# unitbase_anayuki.net
KiCad netlist of a schematic drawn in EAGLE
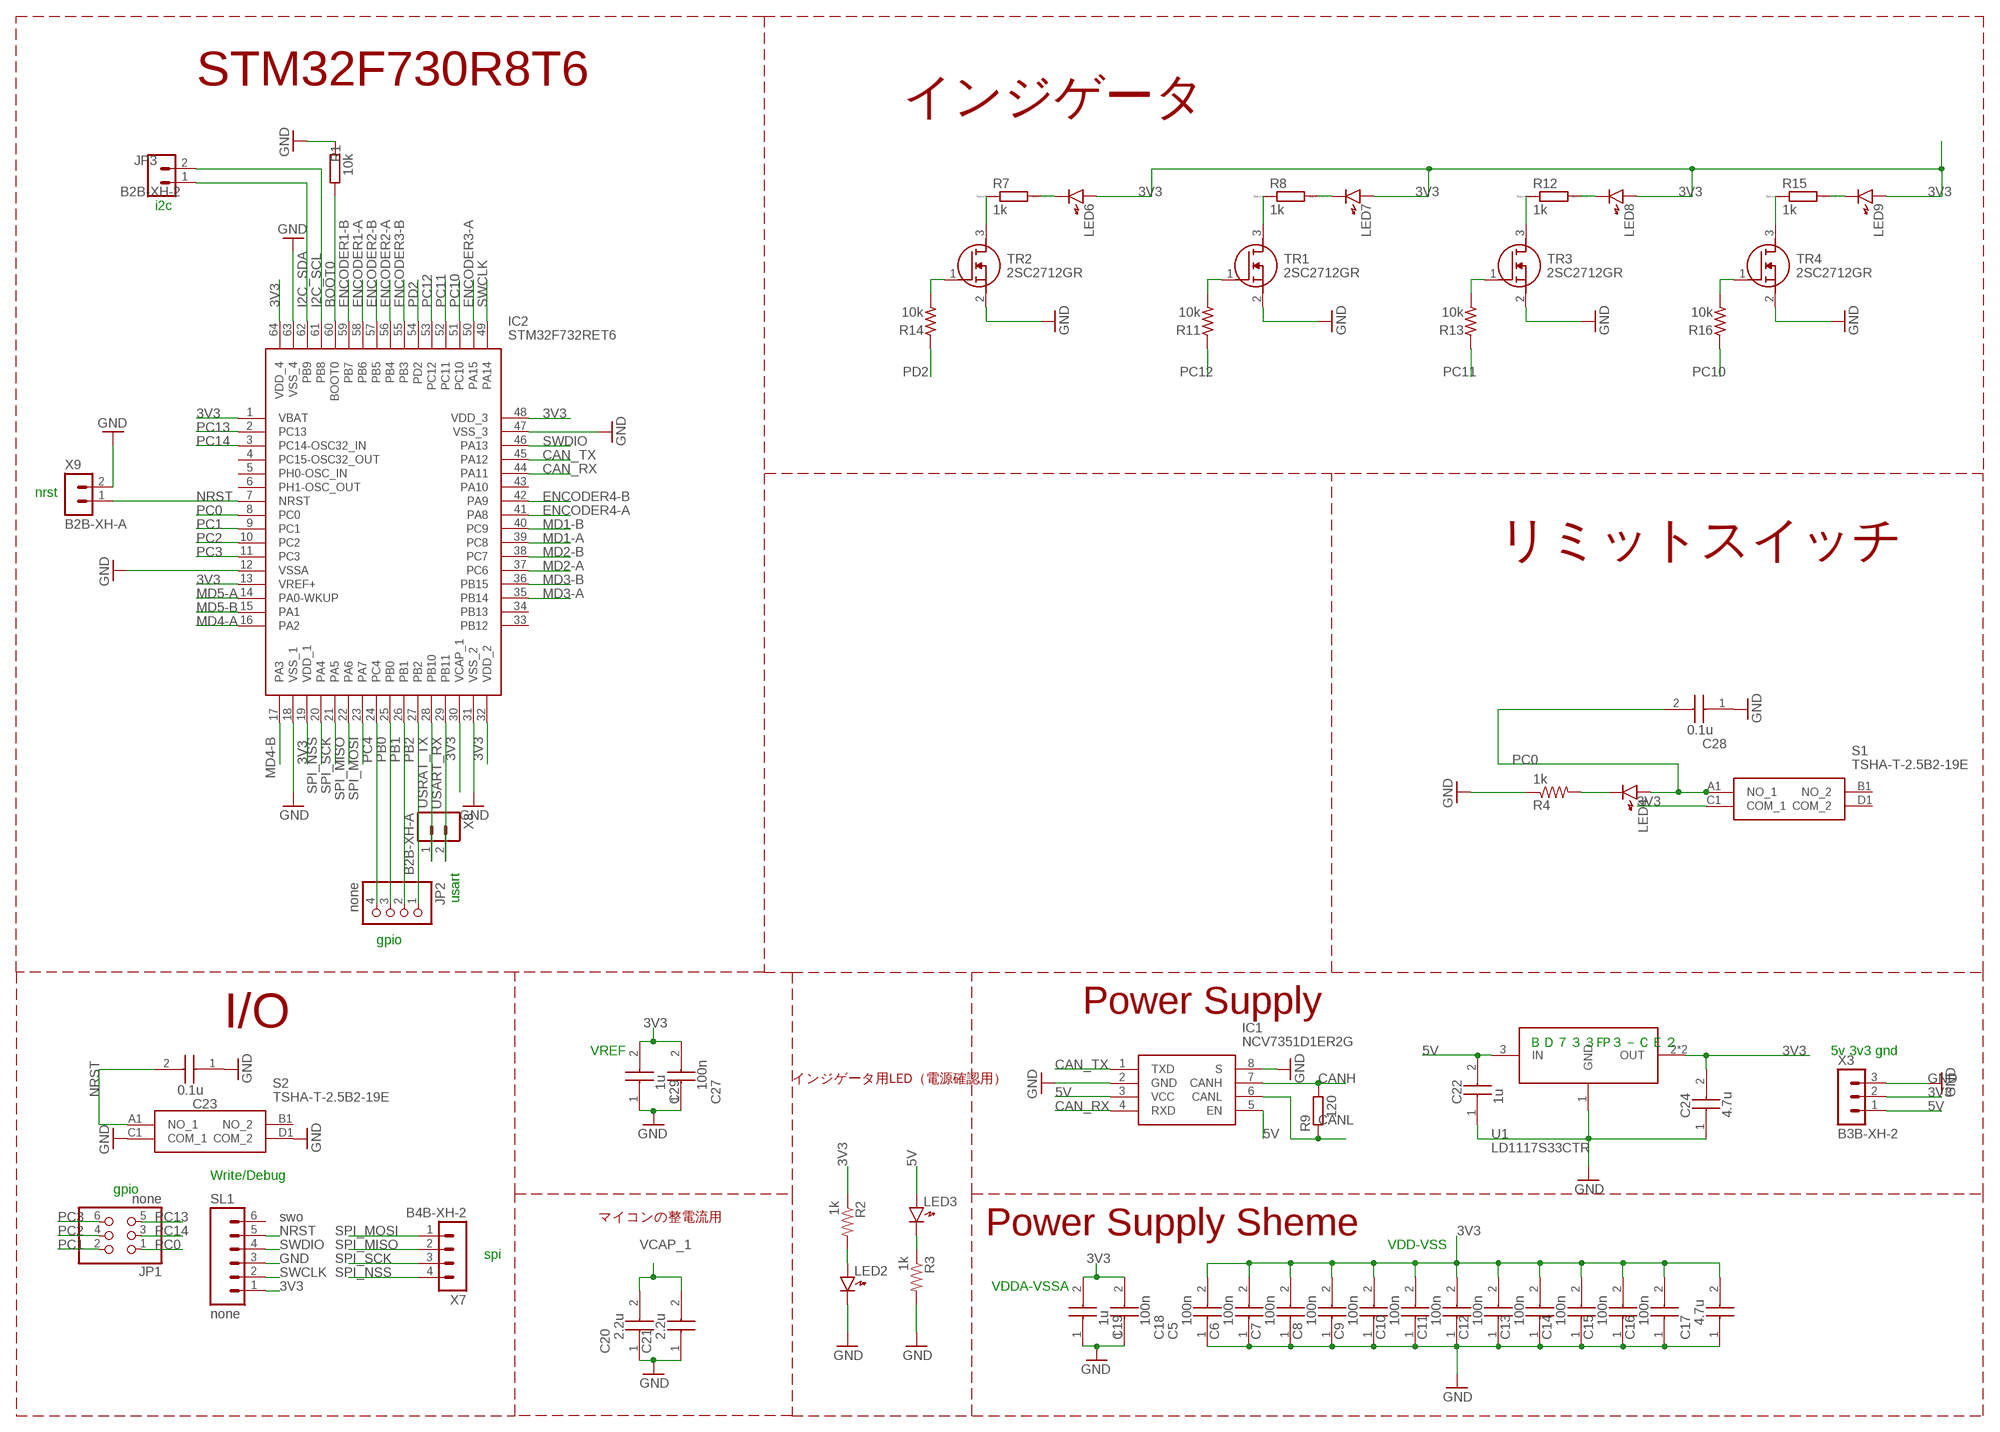
[diagram p0: schematic, sheet 1]
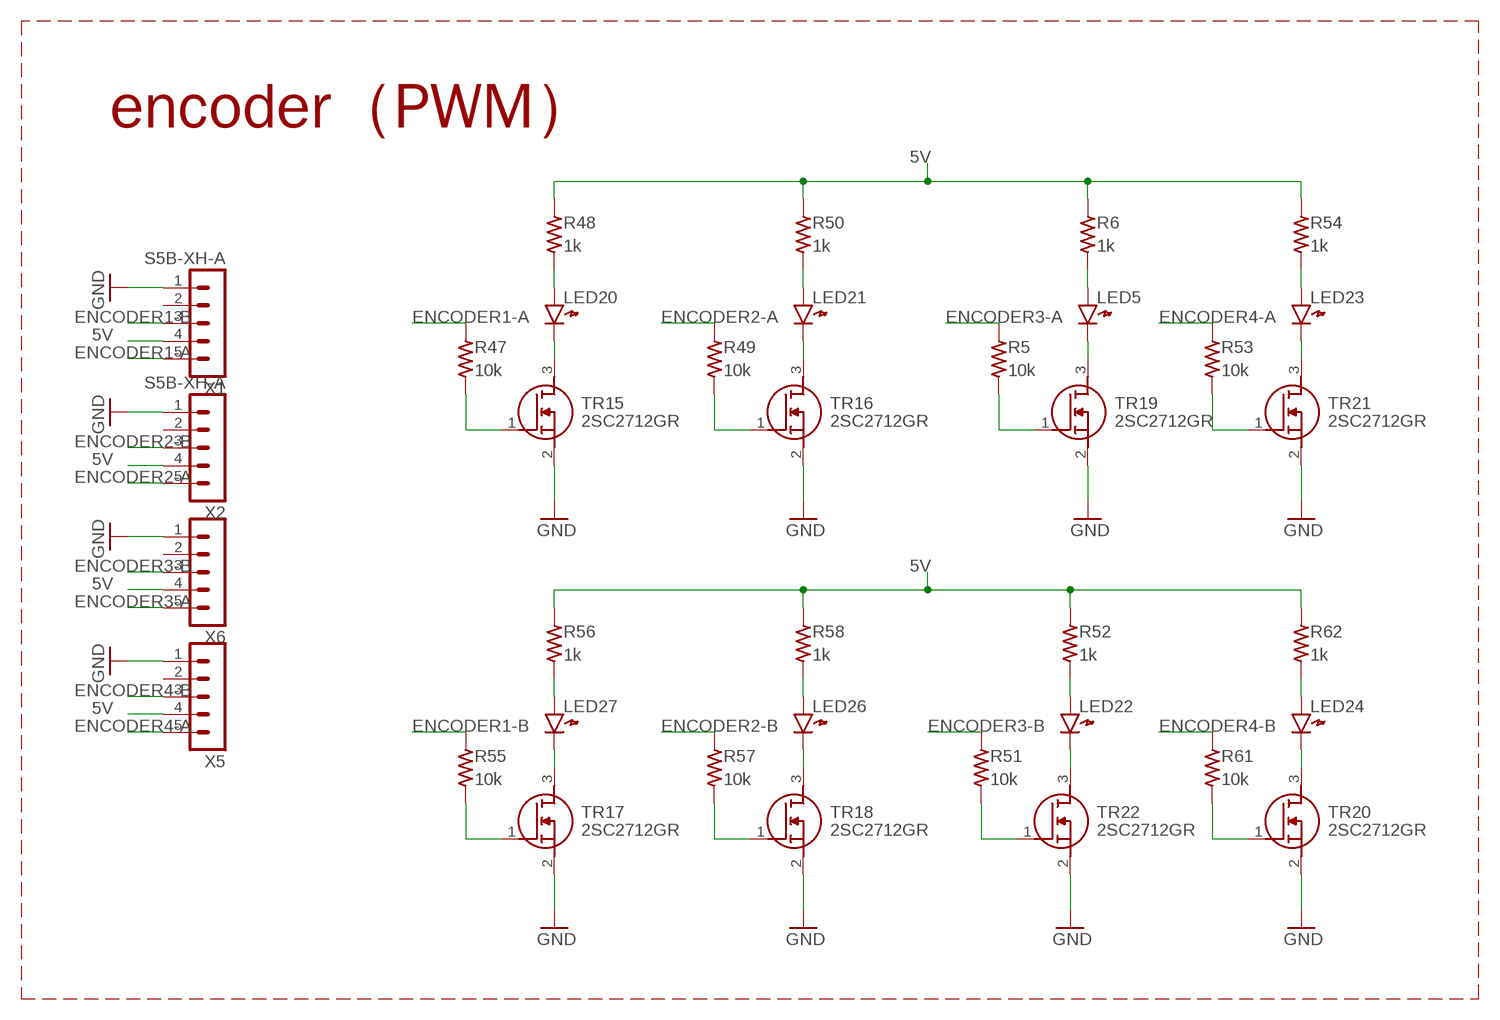
[diagram p1: schematic, sheet 2]
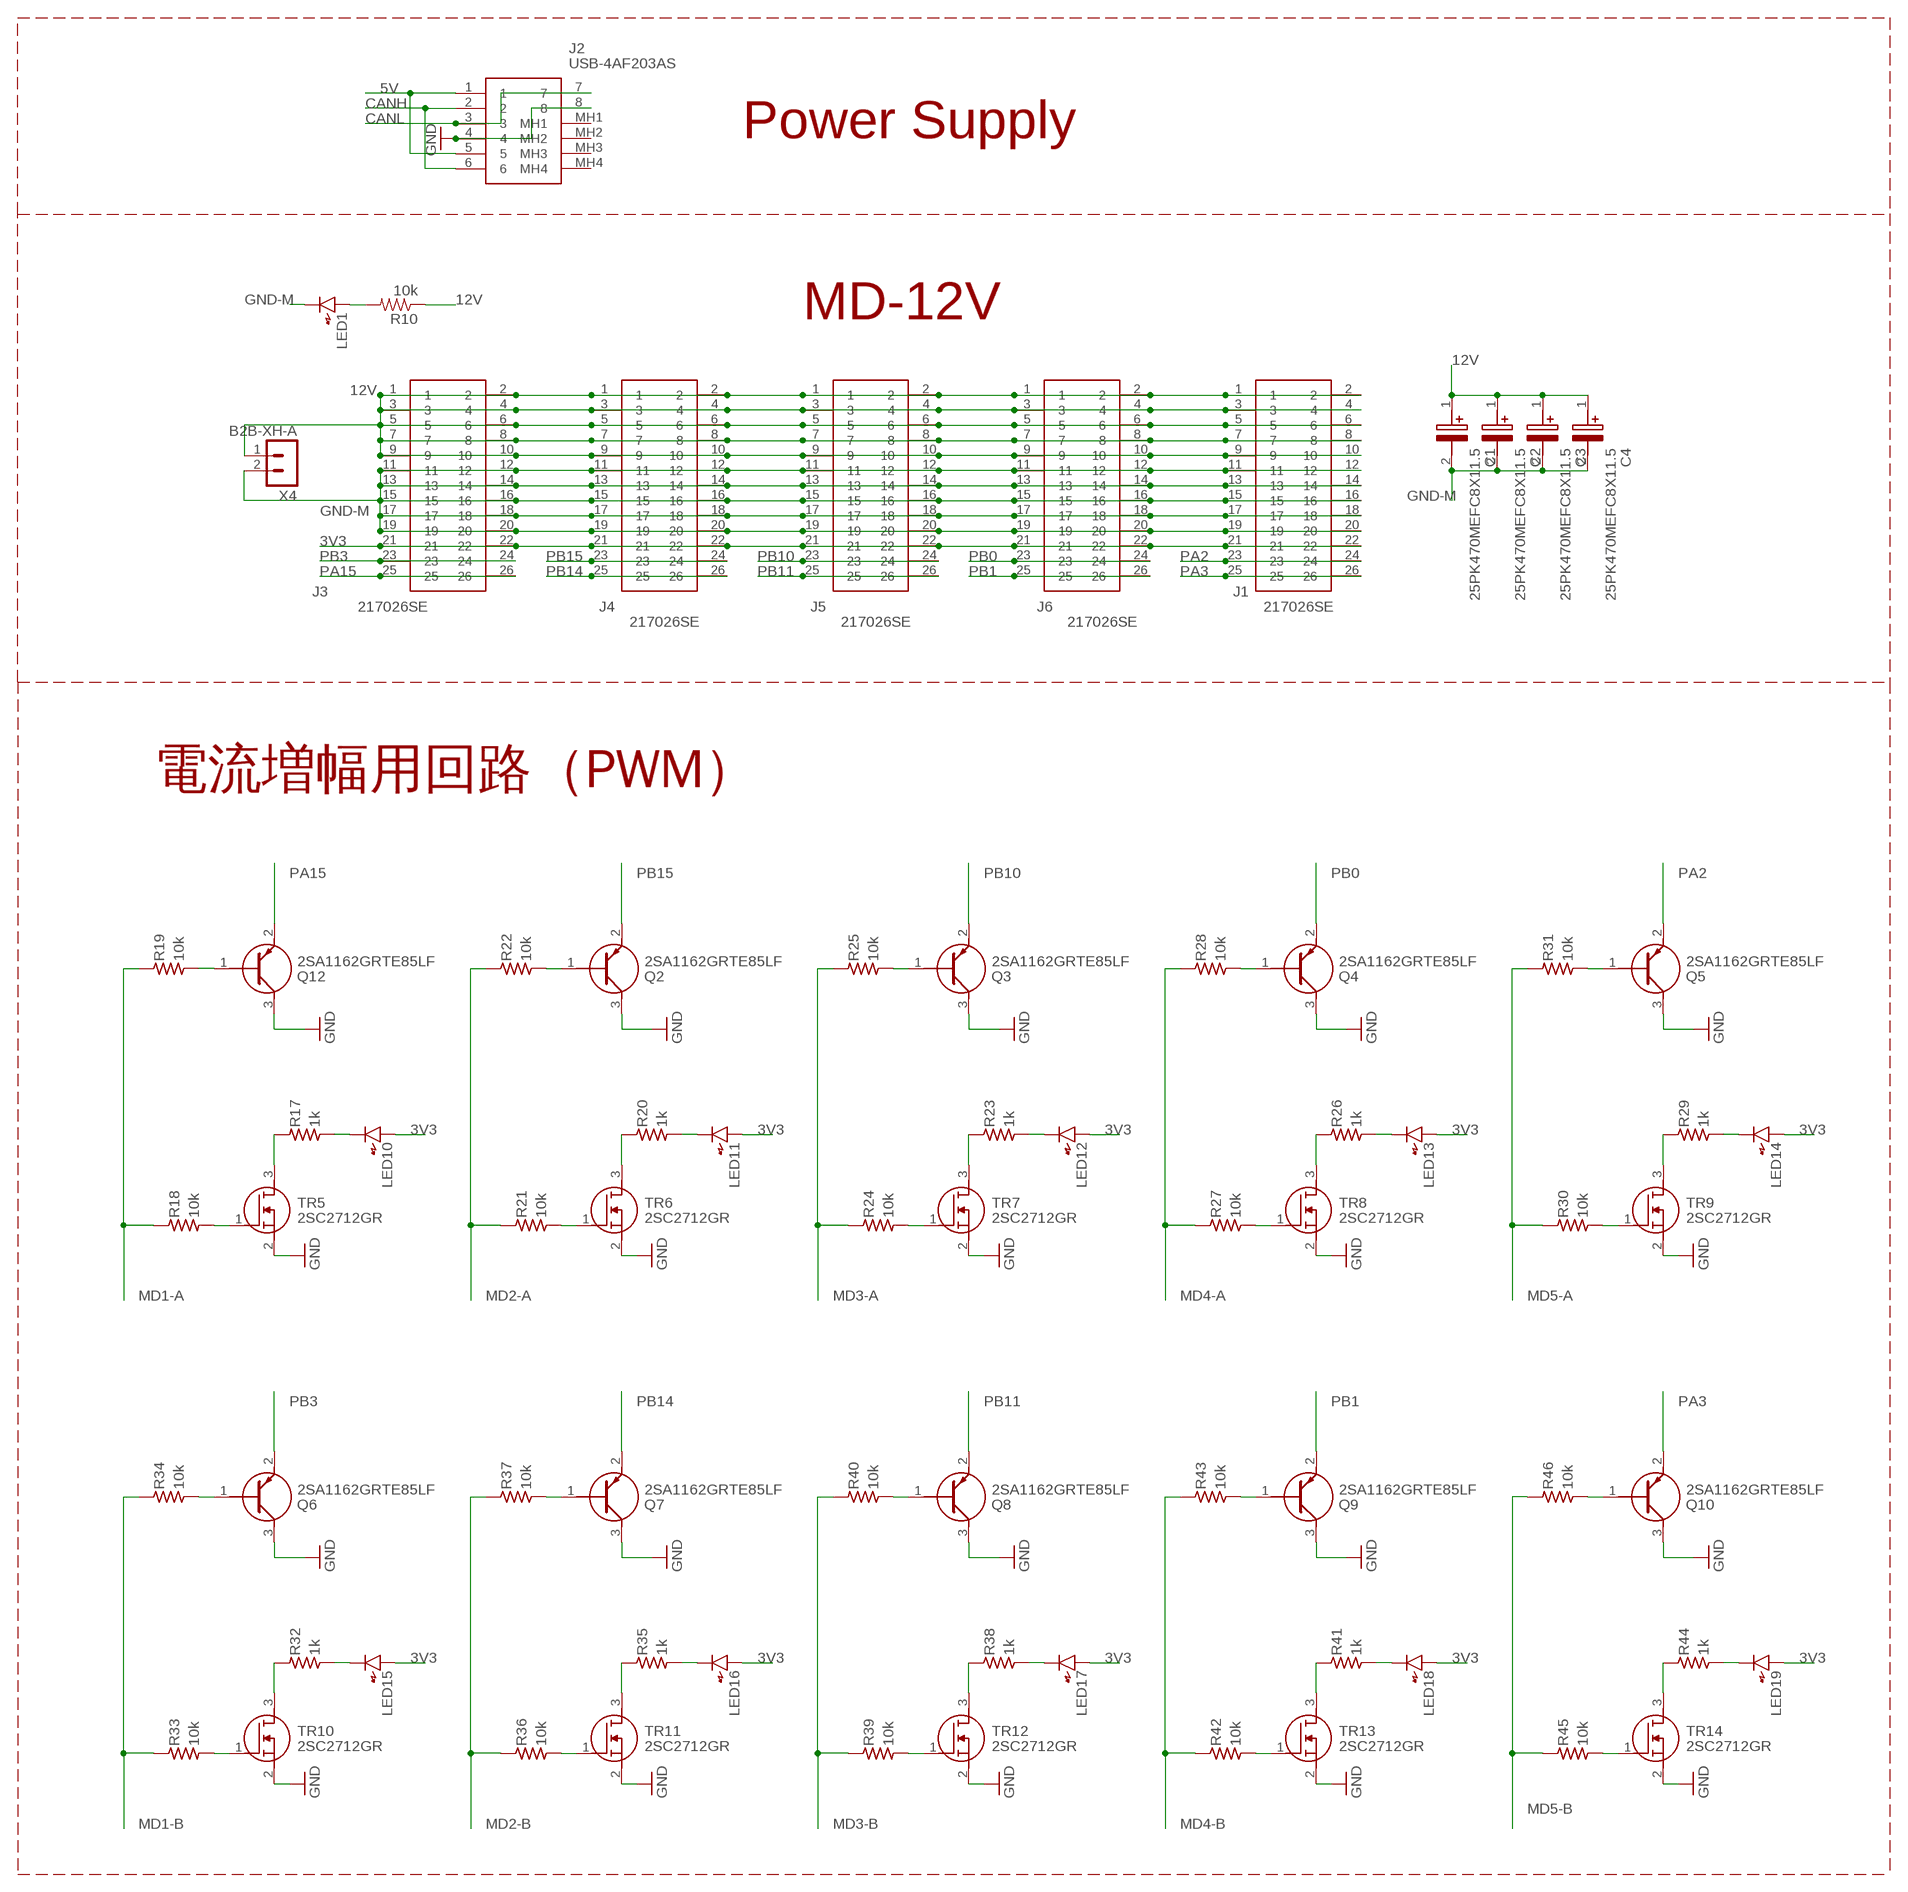
[diagram p2: schematic, sheet 3]

(export (version "E")
  (design (tool "Eeschema 10.0.6"))
  (components
    (comp (ref "C1")
      (value "25PK470MEFC8X11.5")
      (footprint "eagle-import:CAPPRD350W60D825H1150")
      (fields (field (name "MOUSER_PART_NUMBER") "232-25PK470MEFC8X115"))
      (libsource (lib "eagle-import") (part "25PK470MEFC8X11.5"))
    )
    (comp (ref "C2")
      (value "25PK470MEFC8X11.5")
      (footprint "eagle-import:CAPPRD350W60D825H1150")
      (fields (field (name "MOUSER_PART_NUMBER") "232-25PK470MEFC8X115"))
      (libsource (lib "eagle-import") (part "25PK470MEFC8X11.5"))
    )
    (comp (ref "C3")
      (value "25PK470MEFC8X11.5")
      (footprint "eagle-import:CAPPRD350W60D825H1150")
      (fields (field (name "MOUSER_PART_NUMBER") "232-25PK470MEFC8X115"))
      (libsource (lib "eagle-import") (part "25PK470MEFC8X11.5"))
    )
    (comp (ref "C4")
      (value "25PK470MEFC8X11.5")
      (footprint "eagle-import:CAPPRD350W60D825H1150")
      (fields (field (name "MOUSER_PART_NUMBER") "232-25PK470MEFC8X115"))
      (libsource (lib "eagle-import") (part "25PK470MEFC8X11.5"))
    )
    (comp (ref "J1")
      (value "217026SE")
      (footprint "eagle-import:217026SE")
      (libsource (lib "eagle-import") (part "217026SE"))
    )
    (comp (ref "J2")
      (value "USB-4AF203AS")
      (footprint "eagle-import:USB4AF203AS")
      (libsource (lib "eagle-import") (part "USB-4AF203AS"))
    )
    (comp (ref "J3")
      (value "217026SE")
      (footprint "eagle-import:217026SE")
      (libsource (lib "eagle-import") (part "217026SE"))
    )
    (comp (ref "J4")
      (value "217026SE")
      (footprint "eagle-import:217026SE")
      (libsource (lib "eagle-import") (part "217026SE"))
    )
    (comp (ref "J5")
      (value "217026SE")
      (footprint "eagle-import:217026SE")
      (libsource (lib "eagle-import") (part "217026SE"))
    )
    (comp (ref "J6")
      (value "217026SE")
      (footprint "eagle-import:217026SE")
      (libsource (lib "eagle-import") (part "217026SE"))
    )
    (comp (ref "LED1")
      (value "LED1608")
      (footprint "eagle-import:LED1608")
      (libsource (lib "eagle-import") (part "LED1608"))
    )
    (comp (ref "LED10")
      (value "LED1608")
      (footprint "eagle-import:LED1608")
      (libsource (lib "eagle-import") (part "LED1608"))
    )
    (comp (ref "LED11")
      (value "LED1608")
      (footprint "eagle-import:LED1608")
      (libsource (lib "eagle-import") (part "LED1608"))
    )
    (comp (ref "LED12")
      (value "LED1608")
      (footprint "eagle-import:LED1608")
      (libsource (lib "eagle-import") (part "LED1608"))
    )
    (comp (ref "LED13")
      (value "LED1608")
      (footprint "eagle-import:LED1608")
      (libsource (lib "eagle-import") (part "LED1608"))
    )
    (comp (ref "LED14")
      (value "LED1608")
      (footprint "eagle-import:LED1608")
      (libsource (lib "eagle-import") (part "LED1608"))
    )
    (comp (ref "LED15")
      (value "LED1608")
      (footprint "eagle-import:LED1608")
      (libsource (lib "eagle-import") (part "LED1608"))
    )
    (comp (ref "LED16")
      (value "LED1608")
      (footprint "eagle-import:LED1608")
      (libsource (lib "eagle-import") (part "LED1608"))
    )
    (comp (ref "LED17")
      (value "LED1608")
      (footprint "eagle-import:LED1608")
      (libsource (lib "eagle-import") (part "LED1608"))
    )
    (comp (ref "LED18")
      (value "LED1608")
      (footprint "eagle-import:LED1608")
      (libsource (lib "eagle-import") (part "LED1608"))
    )
    (comp (ref "LED19")
      (value "LED1608")
      (footprint "eagle-import:LED1608")
      (libsource (lib "eagle-import") (part "LED1608"))
    )
    (comp (ref "Q2")
      (value "2SA1162GRTE85LF")
      (footprint "eagle-import:2SA1162GRTE85LF")
      (libsource (lib "eagle-import") (part "2SA1162GRTE85LF"))
    )
    (comp (ref "Q3")
      (value "2SA1162GRTE85LF")
      (footprint "eagle-import:2SA1162GRTE85LF")
      (libsource (lib "eagle-import") (part "2SA1162GRTE85LF"))
    )
    (comp (ref "Q4")
      (value "2SA1162GRTE85LF")
      (footprint "eagle-import:2SA1162GRTE85LF")
      (libsource (lib "eagle-import") (part "2SA1162GRTE85LF"))
    )
    (comp (ref "Q5")
      (value "2SA1162GRTE85LF")
      (footprint "eagle-import:2SA1162GRTE85LF")
      (libsource (lib "eagle-import") (part "2SA1162GRTE85LF"))
    )
    (comp (ref "Q6")
      (value "2SA1162GRTE85LF")
      (footprint "eagle-import:2SA1162GRTE85LF")
      (libsource (lib "eagle-import") (part "2SA1162GRTE85LF"))
    )
    (comp (ref "Q7")
      (value "2SA1162GRTE85LF")
      (footprint "eagle-import:2SA1162GRTE85LF")
      (libsource (lib "eagle-import") (part "2SA1162GRTE85LF"))
    )
    (comp (ref "Q8")
      (value "2SA1162GRTE85LF")
      (footprint "eagle-import:2SA1162GRTE85LF")
      (libsource (lib "eagle-import") (part "2SA1162GRTE85LF"))
    )
    (comp (ref "Q9")
      (value "2SA1162GRTE85LF")
      (footprint "eagle-import:2SA1162GRTE85LF")
      (libsource (lib "eagle-import") (part "2SA1162GRTE85LF"))
    )
    (comp (ref "Q10")
      (value "2SA1162GRTE85LF")
      (footprint "eagle-import:2SA1162GRTE85LF")
      (libsource (lib "eagle-import") (part "2SA1162GRTE85LF"))
    )
    (comp (ref "Q12")
      (value "2SA1162GRTE85LF")
      (footprint "eagle-import:2SA1162GRTE85LF")
      (libsource (lib "eagle-import") (part "2SA1162GRTE85LF"))
    )
    (comp (ref "R10")
      (value "10k")
      (footprint "eagle-import:R0603")
      (libsource (lib "eagle-import") (part "R-US_R0603"))
    )
    (comp (ref "R17")
      (value "1k")
      (footprint "eagle-import:SMD1608")
      (libsource (lib "eagle-import") (part "RESISTOR-US1608"))
    )
    (comp (ref "R18")
      (value "10k")
      (footprint "eagle-import:SMD1608")
      (libsource (lib "eagle-import") (part "RESISTOR-US1608"))
    )
    (comp (ref "R19")
      (value "10k")
      (footprint "eagle-import:SMD1608")
      (libsource (lib "eagle-import") (part "RESISTOR-US1608"))
    )
    (comp (ref "R20")
      (value "1k")
      (footprint "eagle-import:SMD1608")
      (libsource (lib "eagle-import") (part "RESISTOR-US1608"))
    )
    (comp (ref "R21")
      (value "10k")
      (footprint "eagle-import:SMD1608")
      (libsource (lib "eagle-import") (part "RESISTOR-US1608"))
    )
    (comp (ref "R22")
      (value "10k")
      (footprint "eagle-import:SMD1608")
      (libsource (lib "eagle-import") (part "RESISTOR-US1608"))
    )
    (comp (ref "R23")
      (value "1k")
      (footprint "eagle-import:SMD1608")
      (libsource (lib "eagle-import") (part "RESISTOR-US1608"))
    )
    (comp (ref "R24")
      (value "10k")
      (footprint "eagle-import:SMD1608")
      (libsource (lib "eagle-import") (part "RESISTOR-US1608"))
    )
    (comp (ref "R25")
      (value "10k")
      (footprint "eagle-import:SMD1608")
      (libsource (lib "eagle-import") (part "RESISTOR-US1608"))
    )
    (comp (ref "R26")
      (value "1k")
      (footprint "eagle-import:SMD1608")
      (libsource (lib "eagle-import") (part "RESISTOR-US1608"))
    )
    (comp (ref "R27")
      (value "10k")
      (footprint "eagle-import:SMD1608")
      (libsource (lib "eagle-import") (part "RESISTOR-US1608"))
    )
    (comp (ref "R28")
      (value "10k")
      (footprint "eagle-import:SMD1608")
      (libsource (lib "eagle-import") (part "RESISTOR-US1608"))
    )
    (comp (ref "R29")
      (value "1k")
      (footprint "eagle-import:SMD1608")
      (libsource (lib "eagle-import") (part "RESISTOR-US1608"))
    )
    (comp (ref "R30")
      (value "10k")
      (footprint "eagle-import:SMD1608")
      (libsource (lib "eagle-import") (part "RESISTOR-US1608"))
    )
    (comp (ref "R31")
      (value "10k")
      (footprint "eagle-import:SMD1608")
      (libsource (lib "eagle-import") (part "RESISTOR-US1608"))
    )
    (comp (ref "R32")
      (value "1k")
      (footprint "eagle-import:SMD1608")
      (libsource (lib "eagle-import") (part "RESISTOR-US1608"))
    )
    (comp (ref "R33")
      (value "10k")
      (footprint "eagle-import:SMD1608")
      (libsource (lib "eagle-import") (part "RESISTOR-US1608"))
    )
    (comp (ref "R34")
      (value "10k")
      (footprint "eagle-import:SMD1608")
      (libsource (lib "eagle-import") (part "RESISTOR-US1608"))
    )
    (comp (ref "R35")
      (value "1k")
      (footprint "eagle-import:SMD1608")
      (libsource (lib "eagle-import") (part "RESISTOR-US1608"))
    )
    (comp (ref "R36")
      (value "10k")
      (footprint "eagle-import:SMD1608")
      (libsource (lib "eagle-import") (part "RESISTOR-US1608"))
    )
    (comp (ref "R37")
      (value "10k")
      (footprint "eagle-import:SMD1608")
      (libsource (lib "eagle-import") (part "RESISTOR-US1608"))
    )
    (comp (ref "R38")
      (value "1k")
      (footprint "eagle-import:SMD1608")
      (libsource (lib "eagle-import") (part "RESISTOR-US1608"))
    )
    (comp (ref "R39")
      (value "10k")
      (footprint "eagle-import:SMD1608")
      (libsource (lib "eagle-import") (part "RESISTOR-US1608"))
    )
    (comp (ref "R40")
      (value "10k")
      (footprint "eagle-import:SMD1608")
      (libsource (lib "eagle-import") (part "RESISTOR-US1608"))
    )
    (comp (ref "R41")
      (value "1k")
      (footprint "eagle-import:SMD1608")
      (libsource (lib "eagle-import") (part "RESISTOR-US1608"))
    )
    (comp (ref "R42")
      (value "10k")
      (footprint "eagle-import:SMD1608")
      (libsource (lib "eagle-import") (part "RESISTOR-US1608"))
    )
    (comp (ref "R43")
      (value "10k")
      (footprint "eagle-import:SMD1608")
      (libsource (lib "eagle-import") (part "RESISTOR-US1608"))
    )
    (comp (ref "R44")
      (value "1k")
      (footprint "eagle-import:SMD1608")
      (libsource (lib "eagle-import") (part "RESISTOR-US1608"))
    )
    (comp (ref "R45")
      (value "10k")
      (footprint "eagle-import:SMD1608")
      (libsource (lib "eagle-import") (part "RESISTOR-US1608"))
    )
    (comp (ref "R46")
      (value "10k")
      (footprint "eagle-import:SMD1608")
      (libsource (lib "eagle-import") (part "RESISTOR-US1608"))
    )
    (comp (ref "TR5")
      (value "2SC2712GR")
      (footprint "eagle-import:SOT-23")
      (libsource (lib "eagle-import") (part "SOT-23_NMOS"))
    )
    (comp (ref "TR6")
      (value "2SC2712GR")
      (footprint "eagle-import:SOT-23")
      (libsource (lib "eagle-import") (part "SOT-23_NMOS"))
    )
    (comp (ref "TR7")
      (value "2SC2712GR")
      (footprint "eagle-import:SOT-23")
      (libsource (lib "eagle-import") (part "SOT-23_NMOS"))
    )
    (comp (ref "TR8")
      (value "2SC2712GR")
      (footprint "eagle-import:SOT-23")
      (libsource (lib "eagle-import") (part "SOT-23_NMOS"))
    )
    (comp (ref "TR9")
      (value "2SC2712GR")
      (footprint "eagle-import:SOT-23")
      (libsource (lib "eagle-import") (part "SOT-23_NMOS"))
    )
    (comp (ref "TR10")
      (value "2SC2712GR")
      (footprint "eagle-import:SOT-23")
      (libsource (lib "eagle-import") (part "SOT-23_NMOS"))
    )
    (comp (ref "TR11")
      (value "2SC2712GR")
      (footprint "eagle-import:SOT-23")
      (libsource (lib "eagle-import") (part "SOT-23_NMOS"))
    )
    (comp (ref "TR12")
      (value "2SC2712GR")
      (footprint "eagle-import:SOT-23")
      (libsource (lib "eagle-import") (part "SOT-23_NMOS"))
    )
    (comp (ref "TR13")
      (value "2SC2712GR")
      (footprint "eagle-import:SOT-23")
      (libsource (lib "eagle-import") (part "SOT-23_NMOS"))
    )
    (comp (ref "TR14")
      (value "2SC2712GR")
      (footprint "eagle-import:SOT-23")
      (libsource (lib "eagle-import") (part "SOT-23_NMOS"))
    )
    (comp (ref "X4")
      (value "B2B-XH-A")
      (footprint "eagle-import:B2B-XH-A")
      (libsource (lib "eagle-import") (part "B2B-XH-A"))
    )
    (comp (ref "LED5")
      (value "LED1608")
      (footprint "eagle-import:LED1608")
      (libsource (lib "eagle-import") (part "LED1608"))
    )
    (comp (ref "LED20")
      (value "LED1608")
      (footprint "eagle-import:LED1608")
      (libsource (lib "eagle-import") (part "LED1608"))
    )
    (comp (ref "LED21")
      (value "LED1608")
      (footprint "eagle-import:LED1608")
      (libsource (lib "eagle-import") (part "LED1608"))
    )
    (comp (ref "LED22")
      (value "LED1608")
      (footprint "eagle-import:LED1608")
      (libsource (lib "eagle-import") (part "LED1608"))
    )
    (comp (ref "LED23")
      (value "LED1608")
      (footprint "eagle-import:LED1608")
      (libsource (lib "eagle-import") (part "LED1608"))
    )
    (comp (ref "LED24")
      (value "LED1608")
      (footprint "eagle-import:LED1608")
      (libsource (lib "eagle-import") (part "LED1608"))
    )
    (comp (ref "LED26")
      (value "LED1608")
      (footprint "eagle-import:LED1608")
      (libsource (lib "eagle-import") (part "LED1608"))
    )
    (comp (ref "LED27")
      (value "LED1608")
      (footprint "eagle-import:LED1608")
      (libsource (lib "eagle-import") (part "LED1608"))
    )
    (comp (ref "R5")
      (value "10k")
      (footprint "eagle-import:SMD1608")
      (libsource (lib "eagle-import") (part "RESISTOR-US1608"))
    )
    (comp (ref "R6")
      (value "1k")
      (footprint "eagle-import:SMD1608")
      (libsource (lib "eagle-import") (part "RESISTOR-US1608"))
    )
    (comp (ref "R47")
      (value "10k")
      (footprint "eagle-import:SMD1608")
      (libsource (lib "eagle-import") (part "RESISTOR-US1608"))
    )
    (comp (ref "R48")
      (value "1k")
      (footprint "eagle-import:SMD1608")
      (libsource (lib "eagle-import") (part "RESISTOR-US1608"))
    )
    (comp (ref "R49")
      (value "10k")
      (footprint "eagle-import:SMD1608")
      (libsource (lib "eagle-import") (part "RESISTOR-US1608"))
    )
    (comp (ref "R50")
      (value "1k")
      (footprint "eagle-import:SMD1608")
      (libsource (lib "eagle-import") (part "RESISTOR-US1608"))
    )
    (comp (ref "R51")
      (value "10k")
      (footprint "eagle-import:SMD1608")
      (libsource (lib "eagle-import") (part "RESISTOR-US1608"))
    )
    (comp (ref "R52")
      (value "1k")
      (footprint "eagle-import:SMD1608")
      (libsource (lib "eagle-import") (part "RESISTOR-US1608"))
    )
    (comp (ref "R53")
      (value "10k")
      (footprint "eagle-import:SMD1608")
      (libsource (lib "eagle-import") (part "RESISTOR-US1608"))
    )
    (comp (ref "R54")
      (value "1k")
      (footprint "eagle-import:SMD1608")
      (libsource (lib "eagle-import") (part "RESISTOR-US1608"))
    )
    (comp (ref "R55")
      (value "10k")
      (footprint "eagle-import:SMD1608")
      (libsource (lib "eagle-import") (part "RESISTOR-US1608"))
    )
    (comp (ref "R56")
      (value "1k")
      (footprint "eagle-import:SMD1608")
      (libsource (lib "eagle-import") (part "RESISTOR-US1608"))
    )
    (comp (ref "R57")
      (value "10k")
      (footprint "eagle-import:SMD1608")
      (libsource (lib "eagle-import") (part "RESISTOR-US1608"))
    )
    (comp (ref "R58")
      (value "1k")
      (footprint "eagle-import:SMD1608")
      (libsource (lib "eagle-import") (part "RESISTOR-US1608"))
    )
    (comp (ref "R61")
      (value "10k")
      (footprint "eagle-import:SMD1608")
      (libsource (lib "eagle-import") (part "RESISTOR-US1608"))
    )
    (comp (ref "R62")
      (value "1k")
      (footprint "eagle-import:SMD1608")
      (libsource (lib "eagle-import") (part "RESISTOR-US1608"))
    )
    (comp (ref "TR15")
      (value "2SC2712GR")
      (footprint "eagle-import:SOT-23")
      (libsource (lib "eagle-import") (part "SOT-23_NMOS"))
    )
    (comp (ref "TR16")
      (value "2SC2712GR")
      (footprint "eagle-import:SOT-23")
      (libsource (lib "eagle-import") (part "SOT-23_NMOS"))
    )
    (comp (ref "TR17")
      (value "2SC2712GR")
      (footprint "eagle-import:SOT-23")
      (libsource (lib "eagle-import") (part "SOT-23_NMOS"))
    )
    (comp (ref "TR18")
      (value "2SC2712GR")
      (footprint "eagle-import:SOT-23")
      (libsource (lib "eagle-import") (part "SOT-23_NMOS"))
    )
    (comp (ref "TR19")
      (value "2SC2712GR")
      (footprint "eagle-import:SOT-23")
      (libsource (lib "eagle-import") (part "SOT-23_NMOS"))
    )
    (comp (ref "TR20")
      (value "2SC2712GR")
      (footprint "eagle-import:SOT-23")
      (libsource (lib "eagle-import") (part "SOT-23_NMOS"))
    )
    (comp (ref "TR21")
      (value "2SC2712GR")
      (footprint "eagle-import:SOT-23")
      (libsource (lib "eagle-import") (part "SOT-23_NMOS"))
    )
    (comp (ref "TR22")
      (value "2SC2712GR")
      (footprint "eagle-import:SOT-23")
      (libsource (lib "eagle-import") (part "SOT-23_NMOS"))
    )
    (comp (ref "X1")
      (value "S5B-XH-A")
      (footprint "eagle-import:S5B-XH-A")
      (libsource (lib "eagle-import") (part "S5B-XH-A"))
    )
    (comp (ref "X2")
      (value "S5B-XH-A")
      (footprint "eagle-import:S5B-XH-A")
      (libsource (lib "eagle-import") (part "S5B-XH-A"))
    )
    (comp (ref "X5")
      (value "S5B-XH-A")
      (footprint "eagle-import:S5B-XH-A")
      (libsource (lib "eagle-import") (part "S5B-XH-A"))
    )
    (comp (ref "X6")
      (value "S5B-XH-A")
      (footprint "eagle-import:S5B-XH-A")
      (libsource (lib "eagle-import") (part "S5B-XH-A"))
    )
    (comp (ref "C5")
      (value "100n")
      (footprint "eagle-import:CAPC1709X100N")
      (fields
        (field (name "MANUFACTURER_PART_NUMBER") "AMK107BBJ476MA-RE")
        (field (name "MOUSER_PART_NUMBER") "963-AMK107BBJ476MARE")
        (field (name "RS_PART_NUMBER") "1843762P")
      )
      (libsource (lib "eagle-import") (part "AMK107BBJ476MA-RE"))
    )
    (comp (ref "C6")
      (value "100n")
      (footprint "eagle-import:CAPC1709X100N")
      (fields
        (field (name "MANUFACTURER_PART_NUMBER") "AMK107BBJ476MA-RE")
        (field (name "MOUSER_PART_NUMBER") "963-AMK107BBJ476MARE")
        (field (name "RS_PART_NUMBER") "1843762P")
      )
      (libsource (lib "eagle-import") (part "AMK107BBJ476MA-RE"))
    )
    (comp (ref "C7")
      (value "100n")
      (footprint "eagle-import:CAPC1709X100N")
      (fields
        (field (name "MANUFACTURER_PART_NUMBER") "AMK107BBJ476MA-RE")
        (field (name "MOUSER_PART_NUMBER") "963-AMK107BBJ476MARE")
        (field (name "RS_PART_NUMBER") "1843762P")
      )
      (libsource (lib "eagle-import") (part "AMK107BBJ476MA-RE"))
    )
    (comp (ref "C8")
      (value "100n")
      (footprint "eagle-import:CAPC1709X100N")
      (fields
        (field (name "MANUFACTURER_PART_NUMBER") "AMK107BBJ476MA-RE")
        (field (name "MOUSER_PART_NUMBER") "963-AMK107BBJ476MARE")
        (field (name "RS_PART_NUMBER") "1843762P")
      )
      (libsource (lib "eagle-import") (part "AMK107BBJ476MA-RE"))
    )
    (comp (ref "C9")
      (value "100n")
      (footprint "eagle-import:CAPC1709X100N")
      (fields
        (field (name "MANUFACTURER_PART_NUMBER") "AMK107BBJ476MA-RE")
        (field (name "MOUSER_PART_NUMBER") "963-AMK107BBJ476MARE")
        (field (name "RS_PART_NUMBER") "1843762P")
      )
      (libsource (lib "eagle-import") (part "AMK107BBJ476MA-RE"))
    )
    (comp (ref "C10")
      (value "100n")
      (footprint "eagle-import:CAPC1709X100N")
      (fields
        (field (name "MANUFACTURER_PART_NUMBER") "AMK107BBJ476MA-RE")
        (field (name "MOUSER_PART_NUMBER") "963-AMK107BBJ476MARE")
        (field (name "RS_PART_NUMBER") "1843762P")
      )
      (libsource (lib "eagle-import") (part "AMK107BBJ476MA-RE"))
    )
    (comp (ref "C11")
      (value "100n")
      (footprint "eagle-import:CAPC1709X100N")
      (fields
        (field (name "MANUFACTURER_PART_NUMBER") "AMK107BBJ476MA-RE")
        (field (name "MOUSER_PART_NUMBER") "963-AMK107BBJ476MARE")
        (field (name "RS_PART_NUMBER") "1843762P")
      )
      (libsource (lib "eagle-import") (part "AMK107BBJ476MA-RE"))
    )
    (comp (ref "C12")
      (value "100n")
      (footprint "eagle-import:CAPC1709X100N")
      (fields
        (field (name "MANUFACTURER_PART_NUMBER") "AMK107BBJ476MA-RE")
        (field (name "MOUSER_PART_NUMBER") "963-AMK107BBJ476MARE")
        (field (name "RS_PART_NUMBER") "1843762P")
      )
      (libsource (lib "eagle-import") (part "AMK107BBJ476MA-RE"))
    )
    (comp (ref "C13")
      (value "100n")
      (footprint "eagle-import:CAPC1709X100N")
      (fields
        (field (name "MANUFACTURER_PART_NUMBER") "AMK107BBJ476MA-RE")
        (field (name "MOUSER_PART_NUMBER") "963-AMK107BBJ476MARE")
        (field (name "RS_PART_NUMBER") "1843762P")
      )
      (libsource (lib "eagle-import") (part "AMK107BBJ476MA-RE"))
    )
    (comp (ref "C14")
      (value "100n")
      (footprint "eagle-import:CAPC1709X100N")
      (fields
        (field (name "MANUFACTURER_PART_NUMBER") "AMK107BBJ476MA-RE")
        (field (name "MOUSER_PART_NUMBER") "963-AMK107BBJ476MARE")
        (field (name "RS_PART_NUMBER") "1843762P")
      )
      (libsource (lib "eagle-import") (part "AMK107BBJ476MA-RE"))
    )
    (comp (ref "C15")
      (value "100n")
      (footprint "eagle-import:CAPC1709X100N")
      (fields
        (field (name "MANUFACTURER_PART_NUMBER") "AMK107BBJ476MA-RE")
        (field (name "MOUSER_PART_NUMBER") "963-AMK107BBJ476MARE")
        (field (name "RS_PART_NUMBER") "1843762P")
      )
      (libsource (lib "eagle-import") (part "AMK107BBJ476MA-RE"))
    )
    (comp (ref "C16")
      (value "100n")
      (footprint "eagle-import:CAPC1709X100N")
      (fields
        (field (name "MANUFACTURER_PART_NUMBER") "AMK107BBJ476MA-RE")
        (field (name "MOUSER_PART_NUMBER") "963-AMK107BBJ476MARE")
        (field (name "RS_PART_NUMBER") "1843762P")
      )
      (libsource (lib "eagle-import") (part "AMK107BBJ476MA-RE"))
    )
    (comp (ref "C17")
      (value "4.7u")
      (footprint "eagle-import:CAPC1709X100N")
      (fields
        (field (name "MANUFACTURER_PART_NUMBER") "AMK107BBJ476MA-RE")
        (field (name "MOUSER_PART_NUMBER") "963-AMK107BBJ476MARE")
        (field (name "RS_PART_NUMBER") "1843762P")
      )
      (libsource (lib "eagle-import") (part "AMK107BBJ476MA-RE"))
    )
    (comp (ref "C18")
      (value "100n")
      (footprint "eagle-import:CAPC1709X100N")
      (fields
        (field (name "MANUFACTURER_PART_NUMBER") "AMK107BBJ476MA-RE")
        (field (name "MOUSER_PART_NUMBER") "963-AMK107BBJ476MARE")
        (field (name "RS_PART_NUMBER") "1843762P")
      )
      (libsource (lib "eagle-import") (part "AMK107BBJ476MA-RE"))
    )
    (comp (ref "C19")
      (value "1u")
      (footprint "eagle-import:CAPC1709X100N")
      (fields
        (field (name "MANUFACTURER_PART_NUMBER") "AMK107BBJ476MA-RE")
        (field (name "MOUSER_PART_NUMBER") "963-AMK107BBJ476MARE")
        (field (name "RS_PART_NUMBER") "1843762P")
      )
      (libsource (lib "eagle-import") (part "AMK107BBJ476MA-RE"))
    )
    (comp (ref "C20")
      (value "2.2u")
      (footprint "eagle-import:CAPC1709X100N")
      (fields
        (field (name "MANUFACTURER_PART_NUMBER") "AMK107BBJ476MA-RE")
        (field (name "MOUSER_PART_NUMBER") "963-AMK107BBJ476MARE")
        (field (name "RS_PART_NUMBER") "1843762P")
      )
      (libsource (lib "eagle-import") (part "AMK107BBJ476MA-RE"))
    )
    (comp (ref "C21")
      (value "2.2u")
      (footprint "eagle-import:CAPC1709X100N")
      (fields
        (field (name "MANUFACTURER_PART_NUMBER") "AMK107BBJ476MA-RE")
        (field (name "MOUSER_PART_NUMBER") "963-AMK107BBJ476MARE")
        (field (name "RS_PART_NUMBER") "1843762P")
      )
      (libsource (lib "eagle-import") (part "AMK107BBJ476MA-RE"))
    )
    (comp (ref "C22")
      (value "1u")
      (footprint "eagle-import:CAPC1608X90N")
      (fields
        (field (name "MANUFACTURER_PART_NUMBER") "GRM188B31A106KE69D")
        (field (name "RS_PART_NUMBER") "8847157P")
      )
      (libsource (lib "eagle-import") (part "GRM188B31A106KE69D"))
    )
    (comp (ref "C23")
      (value "0.1u")
      (footprint "eagle-import:CAPC1709X100N")
      (fields
        (field (name "MANUFACTURER_PART_NUMBER") "AMK107BBJ476MA-RE")
        (field (name "MOUSER_PART_NUMBER") "963-AMK107BBJ476MARE")
        (field (name "RS_PART_NUMBER") "1843762P")
      )
      (libsource (lib "eagle-import") (part "AMK107BBJ476MA-RE"))
    )
    (comp (ref "C24")
      (value "4.7u")
      (footprint "eagle-import:CAPC1608X90N")
      (fields
        (field (name "MANUFACTURER_PART_NUMBER") "GRM188B31A106KE69D")
        (field (name "RS_PART_NUMBER") "8847157P")
      )
      (libsource (lib "eagle-import") (part "GRM188B31A106KE69D"))
    )
    (comp (ref "C27")
      (value "100n")
      (footprint "eagle-import:CAPC1709X100N")
      (fields
        (field (name "MANUFACTURER_PART_NUMBER") "AMK107BBJ476MA-RE")
        (field (name "MOUSER_PART_NUMBER") "963-AMK107BBJ476MARE")
        (field (name "RS_PART_NUMBER") "1843762P")
      )
      (libsource (lib "eagle-import") (part "AMK107BBJ476MA-RE"))
    )
    (comp (ref "C28")
      (value "0.1u")
      (footprint "eagle-import:CAPC1709X100N")
      (fields
        (field (name "MANUFACTURER_PART_NUMBER") "AMK107BBJ476MA-RE")
        (field (name "MOUSER_PART_NUMBER") "963-AMK107BBJ476MARE")
        (field (name "RS_PART_NUMBER") "1843762P")
      )
      (libsource (lib "eagle-import") (part "AMK107BBJ476MA-RE"))
    )
    (comp (ref "C29")
      (value "1u")
      (footprint "eagle-import:CAPC1709X100N")
      (fields
        (field (name "MANUFACTURER_PART_NUMBER") "AMK107BBJ476MA-RE")
        (field (name "MOUSER_PART_NUMBER") "963-AMK107BBJ476MARE")
        (field (name "RS_PART_NUMBER") "1843762P")
      )
      (libsource (lib "eagle-import") (part "AMK107BBJ476MA-RE"))
    )
    (comp (ref "IC1")
      (value "NCV7351D1ER2G")
      (footprint "eagle-import:SOIC127P600X175-8N")
      (fields (field (name "MOUSER_PART_NUMBER") "863-NCV7351D1ER2G"))
      (libsource (lib "eagle-import") (part "NCV7351D1ER2G"))
    )
    (comp (ref "IC2")
      (value "STM32F732RET6")
      (footprint "eagle-import:QFP50P1200X1200X160-64N")
      (fields (field (name "MOUSER_PART_NUMBER") "511-STM32F732RET6"))
      (libsource (lib "eagle-import") (part "STM32F732RET6"))
    )
    (comp (ref "JP1")
      (value "none")
      (footprint "eagle-import:2X03")
      (libsource (lib "eagle-import") (part "PINHD-2X3"))
    )
    (comp (ref "JP2")
      (value "none")
      (footprint "eagle-import:1X04")
      (libsource (lib "eagle-import") (part "PINHD-1X4"))
    )
    (comp (ref "JP3")
      (value "B2B-XH-2")
      (footprint "eagle-import:B2B-XH-A")
      (libsource (lib "eagle-import") (part "B2B-XH-2"))
    )
    (comp (ref "LED2")
      (value "LED1608")
      (footprint "eagle-import:LED1608")
      (libsource (lib "eagle-import") (part "LED1608"))
    )
    (comp (ref "LED3")
      (value "LED1608")
      (footprint "eagle-import:LED1608")
      (libsource (lib "eagle-import") (part "LED1608"))
    )
    (comp (ref "LED4")
      (value "LED1608")
      (footprint "eagle-import:LED1608")
      (libsource (lib "eagle-import") (part "LED1608"))
    )
    (comp (ref "LED6")
      (value "LED1608")
      (footprint "eagle-import:LED1608")
      (libsource (lib "eagle-import") (part "LED1608"))
    )
    (comp (ref "LED7")
      (value "LED1608")
      (footprint "eagle-import:LED1608")
      (libsource (lib "eagle-import") (part "LED1608"))
    )
    (comp (ref "LED8")
      (value "LED1608")
      (footprint "eagle-import:LED1608")
      (libsource (lib "eagle-import") (part "LED1608"))
    )
    (comp (ref "LED9")
      (value "LED1608")
      (footprint "eagle-import:LED1608")
      (libsource (lib "eagle-import") (part "LED1608"))
    )
    (comp (ref "R1")
      (value "10k")
      (footprint "eagle-import:1608")
      (libsource (lib "eagle-import") (part "R1608"))
    )
    (comp (ref "R2")
      (value "1k")
      (footprint "eagle-import:R0603")
      (libsource (lib "eagle-import") (part "R-US_R0603"))
    )
    (comp (ref "R3")
      (value "1k")
      (footprint "eagle-import:R0603")
      (libsource (lib "eagle-import") (part "R-US_R0603"))
    )
    (comp (ref "R4")
      (value "1k")
      (footprint "eagle-import:R0603")
      (libsource (lib "eagle-import") (part "R-US_R0603"))
    )
    (comp (ref "R7")
      (value "1k")
      (footprint "eagle-import:R0603")
      (libsource (lib "eagle-import") (part "RR0603"))
    )
    (comp (ref "R8")
      (value "1k")
      (footprint "eagle-import:R0603")
      (libsource (lib "eagle-import") (part "RR0603"))
    )
    (comp (ref "R9")
      (value "120")
      (footprint "eagle-import:1608")
      (libsource (lib "eagle-import") (part "R1608"))
    )
    (comp (ref "R11")
      (value "10k")
      (footprint "eagle-import:SMD1608")
      (libsource (lib "eagle-import") (part "RESISTOR-US1608"))
    )
    (comp (ref "R12")
      (value "1k")
      (footprint "eagle-import:R0603")
      (libsource (lib "eagle-import") (part "RR0603"))
    )
    (comp (ref "R13")
      (value "10k")
      (footprint "eagle-import:SMD1608")
      (libsource (lib "eagle-import") (part "RESISTOR-US1608"))
    )
    (comp (ref "R14")
      (value "10k")
      (footprint "eagle-import:SMD1608")
      (libsource (lib "eagle-import") (part "RESISTOR-US1608"))
    )
    (comp (ref "R15")
      (value "1k")
      (footprint "eagle-import:R0603")
      (libsource (lib "eagle-import") (part "RR0603"))
    )
    (comp (ref "R16")
      (value "10k")
      (footprint "eagle-import:SMD1608")
      (libsource (lib "eagle-import") (part "RESISTOR-US1608"))
    )
    (comp (ref "S1")
      (value "TSHA-T-2.5B2-19E")
      (footprint "eagle-import:TSHAT25B219E")
      (libsource (lib "eagle-import") (part "TSHA-T-2.5B2-19E"))
    )
    (comp (ref "S2")
      (value "TSHA-T-2.5B2-19E")
      (footprint "eagle-import:TSHAT25B219E")
      (libsource (lib "eagle-import") (part "TSHA-T-2.5B2-19E"))
    )
    (comp (ref "SL1")
      (value "none")
      (footprint "eagle-import:06PA")
      (libsource (lib "eagle-import") (part "MA06"))
    )
    (comp (ref "TR1")
      (value "2SC2712GR")
      (footprint "eagle-import:SOT-23")
      (libsource (lib "eagle-import") (part "SOT-23_NMOS"))
    )
    (comp (ref "TR2")
      (value "2SC2712GR")
      (footprint "eagle-import:SOT-23")
      (libsource (lib "eagle-import") (part "SOT-23_NMOS"))
    )
    (comp (ref "TR3")
      (value "2SC2712GR")
      (footprint "eagle-import:SOT-23")
      (libsource (lib "eagle-import") (part "SOT-23_NMOS"))
    )
    (comp (ref "TR4")
      (value "2SC2712GR")
      (footprint "eagle-import:SOT-23")
      (libsource (lib "eagle-import") (part "SOT-23_NMOS"))
    )
    (comp (ref "U1")
      (value "LD1117S33CTR")
      (footprint "eagle-import:SOT223")
      (fields (field (name "MF") "STMicroelectronics"))
      (libsource (lib "eagle-import") (part "LD1117S33CTR"))
    )
    (comp (ref "X3")
      (value "B3B-XH-2")
      (footprint "eagle-import:B3B-XH-A")
      (libsource (lib "eagle-import") (part "B3B-XH-2"))
    )
    (comp (ref "X7")
      (value "B4B-XH-2")
      (footprint "eagle-import:B4B-XH-A")
      (libsource (lib "eagle-import") (part "B4B-XH-2"))
    )
    (comp (ref "X8")
      (value "B2B-XH-A")
      (footprint "eagle-import:B2B-XH-A")
      (libsource (lib "eagle-import") (part "B2B-XH-A"))
    )
    (comp (ref "X9")
      (value "B2B-XH-A")
      (footprint "eagle-import:B2B-XH-A")
      (libsource (lib "eagle-import") (part "B2B-XH-A"))
    )
  )
  (nets
    (net (code "1") (name "3V3") (class "Default")
      (node (ref "C10") (pin "2") (pinfunction "2_2") (pintype "bidirectional"))
      (node (ref "C11") (pin "2") (pinfunction "2_2") (pintype "bidirectional"))
      (node (ref "C12") (pin "2") (pinfunction "2_2") (pintype "bidirectional"))
      (node (ref "C13") (pin "2") (pinfunction "2_2") (pintype "bidirectional"))
      (node (ref "C14") (pin "2") (pinfunction "2_2") (pintype "bidirectional"))
      (node (ref "C15") (pin "2") (pinfunction "2_2") (pintype "bidirectional"))
      (node (ref "C16") (pin "2") (pinfunction "2_2") (pintype "bidirectional"))
      (node (ref "C17") (pin "2") (pinfunction "2_2") (pintype "bidirectional"))
      (node (ref "C18") (pin "2") (pinfunction "2_2") (pintype "bidirectional"))
      (node (ref "C19") (pin "2") (pinfunction "2_2") (pintype "bidirectional"))
      (node (ref "C24") (pin "2") (pinfunction "2_2") (pintype "bidirectional"))
      (node (ref "C27") (pin "2") (pinfunction "2_2") (pintype "bidirectional"))
      (node (ref "C29") (pin "2") (pinfunction "2_2") (pintype "bidirectional"))
      (node (ref "C5") (pin "2") (pinfunction "2_2") (pintype "bidirectional"))
      (node (ref "C6") (pin "2") (pinfunction "2_2") (pintype "bidirectional"))
      (node (ref "C7") (pin "2") (pinfunction "2_2") (pintype "bidirectional"))
      (node (ref "C8") (pin "2") (pinfunction "2_2") (pintype "bidirectional"))
      (node (ref "C9") (pin "2") (pinfunction "2_2") (pintype "bidirectional"))
      (node (ref "IC2") (pin "1") (pinfunction "VBAT_1") (pintype "power_in"))
      (node (ref "IC2") (pin "13") (pinfunction "VREF+_13") (pintype "power_in"))
      (node (ref "IC2") (pin "19") (pinfunction "VDD_1_19") (pintype "power_in"))
      (node (ref "IC2") (pin "30") (pinfunction "VCAP_1_30") (pintype "power_in"))
      (node (ref "IC2") (pin "32") (pinfunction "VDD_2_32") (pintype "power_in"))
      (node (ref "IC2") (pin "48") (pinfunction "VDD_3_48") (pintype "power_in"))
      (node (ref "IC2") (pin "64") (pinfunction "VDD_4_64") (pintype "power_in"))
      (node (ref "J1") (pin "21") (pinfunction "21_21") (pintype "bidirectional"))
      (node (ref "J1") (pin "22") (pinfunction "22_22") (pintype "bidirectional"))
      (node (ref "J3") (pin "21") (pinfunction "21_21") (pintype "bidirectional"))
      (node (ref "J3") (pin "22") (pinfunction "22_22") (pintype "bidirectional"))
      (node (ref "J4") (pin "21") (pinfunction "21_21") (pintype "bidirectional"))
      (node (ref "J4") (pin "22") (pinfunction "22_22") (pintype "bidirectional"))
      (node (ref "J5") (pin "21") (pinfunction "21_21") (pintype "bidirectional"))
      (node (ref "J5") (pin "22") (pinfunction "22_22") (pintype "bidirectional"))
      (node (ref "J6") (pin "21") (pinfunction "21_21") (pintype "bidirectional"))
      (node (ref "J6") (pin "22") (pinfunction "22_22") (pintype "bidirectional"))
      (node (ref "LED10") (pin "A") (pinfunction "A_A") (pintype "passive"))
      (node (ref "LED11") (pin "A") (pinfunction "A_A") (pintype "passive"))
      (node (ref "LED12") (pin "A") (pinfunction "A_A") (pintype "passive"))
      (node (ref "LED13") (pin "A") (pinfunction "A_A") (pintype "passive"))
      (node (ref "LED14") (pin "A") (pinfunction "A_A") (pintype "passive"))
      (node (ref "LED15") (pin "A") (pinfunction "A_A") (pintype "passive"))
      (node (ref "LED16") (pin "A") (pinfunction "A_A") (pintype "passive"))
      (node (ref "LED17") (pin "A") (pinfunction "A_A") (pintype "passive"))
      (node (ref "LED18") (pin "A") (pinfunction "A_A") (pintype "passive"))
      (node (ref "LED19") (pin "A") (pinfunction "A_A") (pintype "passive"))
      (node (ref "LED6") (pin "A") (pinfunction "A_A") (pintype "passive"))
      (node (ref "LED7") (pin "A") (pinfunction "A_A") (pintype "passive"))
      (node (ref "LED8") (pin "A") (pinfunction "A_A") (pintype "passive"))
      (node (ref "LED9") (pin "A") (pinfunction "A_A") (pintype "passive"))
      (node (ref "R2") (pin "1") (pinfunction "1_1") (pintype "passive"))
      (node (ref "S1") (pin "C1") (pinfunction "COM_1_C1") (pintype "bidirectional"))
      (node (ref "SL1") (pin "1") (pinfunction "1_1") (pintype "passive"))
      (node (ref "U1") (pin "2") (pinfunction "OUT_2") (pintype "output"))
      (node (ref "U1") (pin "4") (pinfunction "OUT_4") (pintype "output"))
      (node (ref "X3") (pin "2") (pinfunction "2_2") (pintype "passive"))
    )
    (net (code "2") (name "5V") (class "Default")
      (node (ref "C22") (pin "2") (pinfunction "2_2") (pintype "bidirectional"))
      (node (ref "IC1") (pin "3") (pinfunction "VCC_3") (pintype "bidirectional"))
      (node (ref "IC1") (pin "5") (pinfunction "EN_5") (pintype "bidirectional"))
      (node (ref "J2") (pin "1") (pinfunction "1_1") (pintype "bidirectional"))
      (node (ref "J2") (pin "5") (pinfunction "5_5") (pintype "bidirectional"))
      (node (ref "LED3") (pin "A") (pinfunction "A_A") (pintype "passive"))
      (node (ref "R48") (pin "1") (pinfunction "1_1") (pintype "passive"))
      (node (ref "R50") (pin "1") (pinfunction "1_1") (pintype "passive"))
      (node (ref "R52") (pin "1") (pinfunction "1_1") (pintype "passive"))
      (node (ref "R54") (pin "1") (pinfunction "1_1") (pintype "passive"))
      (node (ref "R56") (pin "1") (pinfunction "1_1") (pintype "passive"))
      (node (ref "R58") (pin "1") (pinfunction "1_1") (pintype "passive"))
      (node (ref "R6") (pin "1") (pinfunction "1_1") (pintype "passive"))
      (node (ref "R62") (pin "1") (pinfunction "1_1") (pintype "passive"))
      (node (ref "U1") (pin "3") (pinfunction "IN_3") (pintype "input"))
      (node (ref "X1") (pin "4") (pinfunction "4_4") (pintype "passive"))
      (node (ref "X2") (pin "4") (pinfunction "4_4") (pintype "passive"))
      (node (ref "X3") (pin "1") (pinfunction "1_1") (pintype "passive"))
      (node (ref "X5") (pin "4") (pinfunction "4_4") (pintype "passive"))
      (node (ref "X6") (pin "4") (pinfunction "4_4") (pintype "passive"))
    )
    (net (code "3") (name "12V") (class "Default")
      (node (ref "C1") (pin "1") (pinfunction "+_1") (pintype "bidirectional"))
      (node (ref "C2") (pin "1") (pinfunction "+_1") (pintype "bidirectional"))
      (node (ref "C3") (pin "1") (pinfunction "+_1") (pintype "bidirectional"))
      (node (ref "C4") (pin "1") (pinfunction "+_1") (pintype "bidirectional"))
      (node (ref "J1") (pin "1") (pinfunction "1_1") (pintype "bidirectional"))
      (node (ref "J1") (pin "10") (pinfunction "10_10") (pintype "bidirectional"))
      (node (ref "J1") (pin "2") (pinfunction "2_2") (pintype "bidirectional"))
      (node (ref "J1") (pin "3") (pinfunction "3_3") (pintype "bidirectional"))
      (node (ref "J1") (pin "4") (pinfunction "4_4") (pintype "bidirectional"))
      (node (ref "J1") (pin "5") (pinfunction "5_5") (pintype "bidirectional"))
      (node (ref "J1") (pin "6") (pinfunction "6_6") (pintype "bidirectional"))
      (node (ref "J1") (pin "7") (pinfunction "7_7") (pintype "bidirectional"))
      (node (ref "J1") (pin "8") (pinfunction "8_8") (pintype "bidirectional"))
      (node (ref "J1") (pin "9") (pinfunction "9_9") (pintype "bidirectional"))
      (node (ref "J3") (pin "1") (pinfunction "1_1") (pintype "bidirectional"))
      (node (ref "J3") (pin "10") (pinfunction "10_10") (pintype "bidirectional"))
      (node (ref "J3") (pin "2") (pinfunction "2_2") (pintype "bidirectional"))
      (node (ref "J3") (pin "3") (pinfunction "3_3") (pintype "bidirectional"))
      (node (ref "J3") (pin "4") (pinfunction "4_4") (pintype "bidirectional"))
      (node (ref "J3") (pin "5") (pinfunction "5_5") (pintype "bidirectional"))
      (node (ref "J3") (pin "6") (pinfunction "6_6") (pintype "bidirectional"))
      (node (ref "J3") (pin "7") (pinfunction "7_7") (pintype "bidirectional"))
      (node (ref "J3") (pin "8") (pinfunction "8_8") (pintype "bidirectional"))
      (node (ref "J3") (pin "9") (pinfunction "9_9") (pintype "bidirectional"))
      (node (ref "J4") (pin "1") (pinfunction "1_1") (pintype "bidirectional"))
      (node (ref "J4") (pin "10") (pinfunction "10_10") (pintype "bidirectional"))
      (node (ref "J4") (pin "2") (pinfunction "2_2") (pintype "bidirectional"))
      (node (ref "J4") (pin "3") (pinfunction "3_3") (pintype "bidirectional"))
      (node (ref "J4") (pin "4") (pinfunction "4_4") (pintype "bidirectional"))
      (node (ref "J4") (pin "5") (pinfunction "5_5") (pintype "bidirectional"))
      (node (ref "J4") (pin "6") (pinfunction "6_6") (pintype "bidirectional"))
      (node (ref "J4") (pin "7") (pinfunction "7_7") (pintype "bidirectional"))
      (node (ref "J4") (pin "8") (pinfunction "8_8") (pintype "bidirectional"))
      (node (ref "J4") (pin "9") (pinfunction "9_9") (pintype "bidirectional"))
      (node (ref "J5") (pin "1") (pinfunction "1_1") (pintype "bidirectional"))
      (node (ref "J5") (pin "10") (pinfunction "10_10") (pintype "bidirectional"))
      (node (ref "J5") (pin "2") (pinfunction "2_2") (pintype "bidirectional"))
      (node (ref "J5") (pin "3") (pinfunction "3_3") (pintype "bidirectional"))
      (node (ref "J5") (pin "4") (pinfunction "4_4") (pintype "bidirectional"))
      (node (ref "J5") (pin "5") (pinfunction "5_5") (pintype "bidirectional"))
      (node (ref "J5") (pin "6") (pinfunction "6_6") (pintype "bidirectional"))
      (node (ref "J5") (pin "7") (pinfunction "7_7") (pintype "bidirectional"))
      (node (ref "J5") (pin "8") (pinfunction "8_8") (pintype "bidirectional"))
      (node (ref "J5") (pin "9") (pinfunction "9_9") (pintype "bidirectional"))
      (node (ref "J6") (pin "1") (pinfunction "1_1") (pintype "bidirectional"))
      (node (ref "J6") (pin "10") (pinfunction "10_10") (pintype "bidirectional"))
      (node (ref "J6") (pin "2") (pinfunction "2_2") (pintype "bidirectional"))
      (node (ref "J6") (pin "3") (pinfunction "3_3") (pintype "bidirectional"))
      (node (ref "J6") (pin "4") (pinfunction "4_4") (pintype "bidirectional"))
      (node (ref "J6") (pin "5") (pinfunction "5_5") (pintype "bidirectional"))
      (node (ref "J6") (pin "6") (pinfunction "6_6") (pintype "bidirectional"))
      (node (ref "J6") (pin "7") (pinfunction "7_7") (pintype "bidirectional"))
      (node (ref "J6") (pin "8") (pinfunction "8_8") (pintype "bidirectional"))
      (node (ref "J6") (pin "9") (pinfunction "9_9") (pintype "bidirectional"))
      (node (ref "R10") (pin "1") (pinfunction "1_1") (pintype "passive"))
      (node (ref "X4") (pin "1") (pinfunction "1_1") (pintype "passive"))
    )
    (net (code "4") (name "BOOT0") (class "Default")
      (node (ref "IC2") (pin "60") (pinfunction "BOOT0_60") (pintype "bidirectional"))
      (node (ref "R1") (pin "1") (pinfunction "1_1") (pintype "passive"))
    )
    (net (code "5") (name "CANH") (class "Default")
      (node (ref "IC1") (pin "7") (pinfunction "CANH_7") (pintype "bidirectional"))
      (node (ref "J2") (pin "2") (pinfunction "2_2") (pintype "bidirectional"))
      (node (ref "J2") (pin "6") (pinfunction "6_6") (pintype "bidirectional"))
      (node (ref "R9") (pin "2") (pinfunction "2_2") (pintype "passive"))
    )
    (net (code "6") (name "CANL") (class "Default")
      (node (ref "IC1") (pin "6") (pinfunction "CANL_6") (pintype "bidirectional"))
      (node (ref "J2") (pin "3") (pinfunction "3_3") (pintype "bidirectional"))
      (node (ref "J2") (pin "7") (pinfunction "7_7") (pintype "bidirectional"))
      (node (ref "R9") (pin "1") (pinfunction "1_1") (pintype "passive"))
    )
    (net (code "7") (name "CAN_RX") (class "Default")
      (node (ref "IC1") (pin "4") (pinfunction "RXD_4") (pintype "bidirectional"))
      (node (ref "IC2") (pin "44") (pinfunction "PA11_44") (pintype "bidirectional"))
    )
    (net (code "8") (name "CAN_TX") (class "Default")
      (node (ref "IC1") (pin "1") (pinfunction "TXD_1") (pintype "bidirectional"))
      (node (ref "IC2") (pin "45") (pinfunction "PA12_45") (pintype "bidirectional"))
    )
    (net (code "9") (name "ENCODER1-A") (class "Default")
      (node (ref "IC2") (pin "58") (pinfunction "PB6_58") (pintype "bidirectional"))
      (node (ref "R47") (pin "1") (pinfunction "1_1") (pintype "passive"))
      (node (ref "X1") (pin "5") (pinfunction "5_5") (pintype "passive"))
    )
    (net (code "10") (name "ENCODER1-B") (class "Default")
      (node (ref "IC2") (pin "59") (pinfunction "PB7_59") (pintype "bidirectional"))
      (node (ref "R55") (pin "1") (pinfunction "1_1") (pintype "passive"))
      (node (ref "X1") (pin "3") (pinfunction "3_3") (pintype "passive"))
    )
    (net (code "11") (name "ENCODER2-A") (class "Default")
      (node (ref "IC2") (pin "56") (pinfunction "PB4_56") (pintype "bidirectional"))
      (node (ref "R49") (pin "1") (pinfunction "1_1") (pintype "passive"))
      (node (ref "X2") (pin "5") (pinfunction "5_5") (pintype "passive"))
    )
    (net (code "12") (name "ENCODER2-B") (class "Default")
      (node (ref "IC2") (pin "57") (pinfunction "PB5_57") (pintype "bidirectional"))
      (node (ref "R57") (pin "1") (pinfunction "1_1") (pintype "passive"))
      (node (ref "X2") (pin "3") (pinfunction "3_3") (pintype "passive"))
    )
    (net (code "13") (name "ENCODER3-A") (class "Default")
      (node (ref "IC2") (pin "50") (pinfunction "PA15_50") (pintype "bidirectional"))
      (node (ref "R5") (pin "1") (pinfunction "1_1") (pintype "passive"))
      (node (ref "X6") (pin "5") (pinfunction "5_5") (pintype "passive"))
    )
    (net (code "14") (name "ENCODER3-B") (class "Default")
      (node (ref "IC2") (pin "55") (pinfunction "PB3_55") (pintype "bidirectional"))
      (node (ref "R51") (pin "1") (pinfunction "1_1") (pintype "passive"))
      (node (ref "X6") (pin "3") (pinfunction "3_3") (pintype "passive"))
    )
    (net (code "15") (name "ENCODER4-A") (class "Default")
      (node (ref "IC2") (pin "41") (pinfunction "PA8_41") (pintype "bidirectional"))
      (node (ref "R53") (pin "1") (pinfunction "1_1") (pintype "passive"))
      (node (ref "X5") (pin "5") (pinfunction "5_5") (pintype "passive"))
    )
    (net (code "16") (name "ENCODER4-B") (class "Default")
      (node (ref "IC2") (pin "42") (pinfunction "PA9_42") (pintype "bidirectional"))
      (node (ref "R61") (pin "1") (pinfunction "1_1") (pintype "passive"))
      (node (ref "X5") (pin "3") (pinfunction "3_3") (pintype "passive"))
    )
    (net (code "17") (name "GND") (class "Default")
      (node (ref "C10") (pin "1") (pinfunction "1_1") (pintype "bidirectional"))
      (node (ref "C11") (pin "1") (pinfunction "1_1") (pintype "bidirectional"))
      (node (ref "C12") (pin "1") (pinfunction "1_1") (pintype "bidirectional"))
      (node (ref "C13") (pin "1") (pinfunction "1_1") (pintype "bidirectional"))
      (node (ref "C14") (pin "1") (pinfunction "1_1") (pintype "bidirectional"))
      (node (ref "C15") (pin "1") (pinfunction "1_1") (pintype "bidirectional"))
      (node (ref "C16") (pin "1") (pinfunction "1_1") (pintype "bidirectional"))
      (node (ref "C17") (pin "1") (pinfunction "1_1") (pintype "bidirectional"))
      (node (ref "C18") (pin "1") (pinfunction "1_1") (pintype "bidirectional"))
      (node (ref "C19") (pin "1") (pinfunction "1_1") (pintype "bidirectional"))
      (node (ref "C20") (pin "1") (pinfunction "1_1") (pintype "bidirectional"))
      (node (ref "C21") (pin "1") (pinfunction "1_1") (pintype "bidirectional"))
      (node (ref "C22") (pin "1") (pinfunction "1_1") (pintype "bidirectional"))
      (node (ref "C23") (pin "1") (pinfunction "1_1") (pintype "bidirectional"))
      (node (ref "C24") (pin "1") (pinfunction "1_1") (pintype "bidirectional"))
      (node (ref "C27") (pin "1") (pinfunction "1_1") (pintype "bidirectional"))
      (node (ref "C28") (pin "1") (pinfunction "1_1") (pintype "bidirectional"))
      (node (ref "C29") (pin "1") (pinfunction "1_1") (pintype "bidirectional"))
      (node (ref "C5") (pin "1") (pinfunction "1_1") (pintype "bidirectional"))
      (node (ref "C6") (pin "1") (pinfunction "1_1") (pintype "bidirectional"))
      (node (ref "C7") (pin "1") (pinfunction "1_1") (pintype "bidirectional"))
      (node (ref "C8") (pin "1") (pinfunction "1_1") (pintype "bidirectional"))
      (node (ref "C9") (pin "1") (pinfunction "1_1") (pintype "bidirectional"))
      (node (ref "IC1") (pin "2") (pinfunction "GND_2") (pintype "bidirectional"))
      (node (ref "IC1") (pin "8") (pinfunction "S_8") (pintype "bidirectional"))
      (node (ref "IC2") (pin "12") (pinfunction "VSSA_12") (pintype "power_in"))
      (node (ref "IC2") (pin "18") (pinfunction "VSS_1_18") (pintype "power_in"))
      (node (ref "IC2") (pin "31") (pinfunction "VSS_2_31") (pintype "power_in"))
      (node (ref "IC2") (pin "47") (pinfunction "VSS_3_47") (pintype "power_in"))
      (node (ref "IC2") (pin "63") (pinfunction "VSS_4_63") (pintype "power_in"))
      (node (ref "J2") (pin "4") (pinfunction "4_4") (pintype "bidirectional"))
      (node (ref "J2") (pin "8") (pinfunction "8_8") (pintype "bidirectional"))
      (node (ref "LED2") (pin "K") (pinfunction "K_K") (pintype "passive"))
      (node (ref "Q10") (pin "3") (pinfunction "C_3") (pintype "bidirectional"))
      (node (ref "Q12") (pin "3") (pinfunction "C_3") (pintype "bidirectional"))
      (node (ref "Q2") (pin "3") (pinfunction "C_3") (pintype "bidirectional"))
      (node (ref "Q3") (pin "3") (pinfunction "C_3") (pintype "bidirectional"))
      (node (ref "Q4") (pin "3") (pinfunction "C_3") (pintype "bidirectional"))
      (node (ref "Q5") (pin "3") (pinfunction "C_3") (pintype "bidirectional"))
      (node (ref "Q6") (pin "3") (pinfunction "C_3") (pintype "bidirectional"))
      (node (ref "Q7") (pin "3") (pinfunction "C_3") (pintype "bidirectional"))
      (node (ref "Q8") (pin "3") (pinfunction "C_3") (pintype "bidirectional"))
      (node (ref "Q9") (pin "3") (pinfunction "C_3") (pintype "bidirectional"))
      (node (ref "R1") (pin "2") (pinfunction "2_2") (pintype "passive"))
      (node (ref "R3") (pin "2") (pinfunction "2_2") (pintype "passive"))
      (node (ref "R4") (pin "1") (pinfunction "1_1") (pintype "passive"))
      (node (ref "S2") (pin "C1") (pinfunction "COM_1_C1") (pintype "bidirectional"))
      (node (ref "S2") (pin "D1") (pinfunction "COM_2_D1") (pintype "bidirectional"))
      (node (ref "SL1") (pin "3") (pinfunction "3_3") (pintype "passive"))
      (node (ref "TR1") (pin "2") (pinfunction "S_2") (pintype "bidirectional"))
      (node (ref "TR10") (pin "2") (pinfunction "S_2") (pintype "bidirectional"))
      (node (ref "TR11") (pin "2") (pinfunction "S_2") (pintype "bidirectional"))
      (node (ref "TR12") (pin "2") (pinfunction "S_2") (pintype "bidirectional"))
      (node (ref "TR13") (pin "2") (pinfunction "S_2") (pintype "bidirectional"))
      (node (ref "TR14") (pin "2") (pinfunction "S_2") (pintype "bidirectional"))
      (node (ref "TR15") (pin "2") (pinfunction "S_2") (pintype "bidirectional"))
      (node (ref "TR16") (pin "2") (pinfunction "S_2") (pintype "bidirectional"))
      (node (ref "TR17") (pin "2") (pinfunction "S_2") (pintype "bidirectional"))
      (node (ref "TR18") (pin "2") (pinfunction "S_2") (pintype "bidirectional"))
      (node (ref "TR19") (pin "2") (pinfunction "S_2") (pintype "bidirectional"))
      (node (ref "TR2") (pin "2") (pinfunction "S_2") (pintype "bidirectional"))
      (node (ref "TR20") (pin "2") (pinfunction "S_2") (pintype "bidirectional"))
      (node (ref "TR21") (pin "2") (pinfunction "S_2") (pintype "bidirectional"))
      (node (ref "TR22") (pin "2") (pinfunction "S_2") (pintype "bidirectional"))
      (node (ref "TR3") (pin "2") (pinfunction "S_2") (pintype "bidirectional"))
      (node (ref "TR4") (pin "2") (pinfunction "S_2") (pintype "bidirectional"))
      (node (ref "TR5") (pin "2") (pinfunction "S_2") (pintype "bidirectional"))
      (node (ref "TR6") (pin "2") (pinfunction "S_2") (pintype "bidirectional"))
      (node (ref "TR7") (pin "2") (pinfunction "S_2") (pintype "bidirectional"))
      (node (ref "TR8") (pin "2") (pinfunction "S_2") (pintype "bidirectional"))
      (node (ref "TR9") (pin "2") (pinfunction "S_2") (pintype "bidirectional"))
      (node (ref "U1") (pin "1") (pinfunction "GND_1") (pintype "passive"))
      (node (ref "X1") (pin "1") (pinfunction "1_1") (pintype "passive"))
      (node (ref "X2") (pin "1") (pinfunction "1_1") (pintype "passive"))
      (node (ref "X3") (pin "3") (pinfunction "3_3") (pintype "passive"))
      (node (ref "X5") (pin "1") (pinfunction "1_1") (pintype "passive"))
      (node (ref "X6") (pin "1") (pinfunction "1_1") (pintype "passive"))
      (node (ref "X9") (pin "2") (pinfunction "2_2") (pintype "passive"))
    )
    (net (code "18") (name "GND-M") (class "Default")
      (node (ref "C1") (pin "2") (pinfunction "-_2") (pintype "bidirectional"))
      (node (ref "C2") (pin "2") (pinfunction "-_2") (pintype "bidirectional"))
      (node (ref "C3") (pin "2") (pinfunction "-_2") (pintype "bidirectional"))
      (node (ref "C4") (pin "2") (pinfunction "-_2") (pintype "bidirectional"))
      (node (ref "J1") (pin "11") (pinfunction "11_11") (pintype "bidirectional"))
      (node (ref "J1") (pin "12") (pinfunction "12_12") (pintype "bidirectional"))
      (node (ref "J1") (pin "13") (pinfunction "13_13") (pintype "bidirectional"))
      (node (ref "J1") (pin "14") (pinfunction "14_14") (pintype "bidirectional"))
      (node (ref "J1") (pin "15") (pinfunction "15_15") (pintype "bidirectional"))
      (node (ref "J1") (pin "16") (pinfunction "16_16") (pintype "bidirectional"))
      (node (ref "J1") (pin "17") (pinfunction "17_17") (pintype "bidirectional"))
      (node (ref "J1") (pin "18") (pinfunction "18_18") (pintype "bidirectional"))
      (node (ref "J1") (pin "19") (pinfunction "19_19") (pintype "bidirectional"))
      (node (ref "J1") (pin "20") (pinfunction "20_20") (pintype "bidirectional"))
      (node (ref "J3") (pin "11") (pinfunction "11_11") (pintype "bidirectional"))
      (node (ref "J3") (pin "12") (pinfunction "12_12") (pintype "bidirectional"))
      (node (ref "J3") (pin "13") (pinfunction "13_13") (pintype "bidirectional"))
      (node (ref "J3") (pin "14") (pinfunction "14_14") (pintype "bidirectional"))
      (node (ref "J3") (pin "15") (pinfunction "15_15") (pintype "bidirectional"))
      (node (ref "J3") (pin "16") (pinfunction "16_16") (pintype "bidirectional"))
      (node (ref "J3") (pin "17") (pinfunction "17_17") (pintype "bidirectional"))
      (node (ref "J3") (pin "18") (pinfunction "18_18") (pintype "bidirectional"))
      (node (ref "J3") (pin "19") (pinfunction "19_19") (pintype "bidirectional"))
      (node (ref "J3") (pin "20") (pinfunction "20_20") (pintype "bidirectional"))
      (node (ref "J4") (pin "11") (pinfunction "11_11") (pintype "bidirectional"))
      (node (ref "J4") (pin "12") (pinfunction "12_12") (pintype "bidirectional"))
      (node (ref "J4") (pin "13") (pinfunction "13_13") (pintype "bidirectional"))
      (node (ref "J4") (pin "14") (pinfunction "14_14") (pintype "bidirectional"))
      (node (ref "J4") (pin "15") (pinfunction "15_15") (pintype "bidirectional"))
      (node (ref "J4") (pin "16") (pinfunction "16_16") (pintype "bidirectional"))
      (node (ref "J4") (pin "17") (pinfunction "17_17") (pintype "bidirectional"))
      (node (ref "J4") (pin "18") (pinfunction "18_18") (pintype "bidirectional"))
      (node (ref "J4") (pin "19") (pinfunction "19_19") (pintype "bidirectional"))
      (node (ref "J4") (pin "20") (pinfunction "20_20") (pintype "bidirectional"))
      (node (ref "J5") (pin "11") (pinfunction "11_11") (pintype "bidirectional"))
      (node (ref "J5") (pin "12") (pinfunction "12_12") (pintype "bidirectional"))
      (node (ref "J5") (pin "13") (pinfunction "13_13") (pintype "bidirectional"))
      (node (ref "J5") (pin "14") (pinfunction "14_14") (pintype "bidirectional"))
      (node (ref "J5") (pin "15") (pinfunction "15_15") (pintype "bidirectional"))
      (node (ref "J5") (pin "16") (pinfunction "16_16") (pintype "bidirectional"))
      (node (ref "J5") (pin "17") (pinfunction "17_17") (pintype "bidirectional"))
      (node (ref "J5") (pin "18") (pinfunction "18_18") (pintype "bidirectional"))
      (node (ref "J5") (pin "19") (pinfunction "19_19") (pintype "bidirectional"))
      (node (ref "J5") (pin "20") (pinfunction "20_20") (pintype "bidirectional"))
      (node (ref "J6") (pin "11") (pinfunction "11_11") (pintype "bidirectional"))
      (node (ref "J6") (pin "12") (pinfunction "12_12") (pintype "bidirectional"))
      (node (ref "J6") (pin "13") (pinfunction "13_13") (pintype "bidirectional"))
      (node (ref "J6") (pin "14") (pinfunction "14_14") (pintype "bidirectional"))
      (node (ref "J6") (pin "15") (pinfunction "15_15") (pintype "bidirectional"))
      (node (ref "J6") (pin "16") (pinfunction "16_16") (pintype "bidirectional"))
      (node (ref "J6") (pin "17") (pinfunction "17_17") (pintype "bidirectional"))
      (node (ref "J6") (pin "18") (pinfunction "18_18") (pintype "bidirectional"))
      (node (ref "J6") (pin "19") (pinfunction "19_19") (pintype "bidirectional"))
      (node (ref "J6") (pin "20") (pinfunction "20_20") (pintype "bidirectional"))
      (node (ref "LED1") (pin "K") (pinfunction "K_K") (pintype "passive"))
      (node (ref "X4") (pin "2") (pinfunction "2_2") (pintype "passive"))
    )
    (net (code "19") (name "I2C_SCL") (class "Default")
      (node (ref "IC2") (pin "61") (pinfunction "PB8_61") (pintype "bidirectional"))
      (node (ref "JP3") (pin "2") (pinfunction "2_2") (pintype "passive"))
    )
    (net (code "20") (name "I2C_SDA") (class "Default")
      (node (ref "IC2") (pin "62") (pinfunction "PB9_62") (pintype "bidirectional"))
      (node (ref "JP3") (pin "1") (pinfunction "1_1") (pintype "passive"))
    )
    (net (code "21") (name "MD1-A") (class "Default")
      (node (ref "IC2") (pin "39") (pinfunction "PC8_39") (pintype "bidirectional"))
      (node (ref "R18") (pin "1") (pinfunction "1_1") (pintype "passive"))
      (node (ref "R19") (pin "1") (pinfunction "1_1") (pintype "passive"))
    )
    (net (code "22") (name "MD1-B") (class "Default")
      (node (ref "IC2") (pin "40") (pinfunction "PC9_40") (pintype "bidirectional"))
      (node (ref "R33") (pin "1") (pinfunction "1_1") (pintype "passive"))
      (node (ref "R34") (pin "1") (pinfunction "1_1") (pintype "passive"))
    )
    (net (code "23") (name "MD2-A") (class "Default")
      (node (ref "IC2") (pin "37") (pinfunction "PC6_37") (pintype "bidirectional"))
      (node (ref "R21") (pin "1") (pinfunction "1_1") (pintype "passive"))
      (node (ref "R22") (pin "1") (pinfunction "1_1") (pintype "passive"))
    )
    (net (code "24") (name "MD2-B") (class "Default")
      (node (ref "IC2") (pin "38") (pinfunction "PC7_38") (pintype "bidirectional"))
      (node (ref "R36") (pin "1") (pinfunction "1_1") (pintype "passive"))
      (node (ref "R37") (pin "1") (pinfunction "1_1") (pintype "passive"))
    )
    (net (code "25") (name "MD3-A") (class "Default")
      (node (ref "IC2") (pin "35") (pinfunction "PB14_35") (pintype "bidirectional"))
      (node (ref "R24") (pin "1") (pinfunction "1_1") (pintype "passive"))
      (node (ref "R25") (pin "1") (pinfunction "1_1") (pintype "passive"))
    )
    (net (code "26") (name "MD3-B") (class "Default")
      (node (ref "IC2") (pin "36") (pinfunction "PB15_36") (pintype "bidirectional"))
      (node (ref "R39") (pin "1") (pinfunction "1_1") (pintype "passive"))
      (node (ref "R40") (pin "1") (pinfunction "1_1") (pintype "passive"))
    )
    (net (code "27") (name "MD4-A") (class "Default")
      (node (ref "IC2") (pin "16") (pinfunction "PA2_16") (pintype "bidirectional"))
      (node (ref "R27") (pin "1") (pinfunction "1_1") (pintype "passive"))
      (node (ref "R28") (pin "1") (pinfunction "1_1") (pintype "passive"))
    )
    (net (code "28") (name "MD4-B") (class "Default")
      (node (ref "IC2") (pin "17") (pinfunction "PA3_17") (pintype "bidirectional"))
      (node (ref "R42") (pin "1") (pinfunction "1_1") (pintype "passive"))
      (node (ref "R43") (pin "1") (pinfunction "1_1") (pintype "passive"))
    )
    (net (code "29") (name "MD5-A") (class "Default")
      (node (ref "IC2") (pin "14") (pinfunction "PA0-WKUP_14") (pintype "bidirectional"))
      (node (ref "R30") (pin "1") (pinfunction "1_1") (pintype "passive"))
      (node (ref "R31") (pin "1") (pinfunction "1_1") (pintype "passive"))
    )
    (net (code "30") (name "MD5-B") (class "Default")
      (node (ref "IC2") (pin "15") (pinfunction "PA1_15") (pintype "bidirectional"))
      (node (ref "R45") (pin "1") (pinfunction "1_1") (pintype "passive"))
      (node (ref "R46") (pin "1") (pinfunction "1_1") (pintype "passive"))
    )
    (net (code "31") (name "NRST") (class "Default")
      (node (ref "C23") (pin "2") (pinfunction "2_2") (pintype "bidirectional"))
      (node (ref "IC2") (pin "7") (pinfunction "NRST_7") (pintype "bidirectional"))
      (node (ref "S2") (pin "A1") (pinfunction "NO_1_A1") (pintype "bidirectional"))
      (node (ref "SL1") (pin "5") (pinfunction "5_5") (pintype "passive"))
      (node (ref "X9") (pin "1") (pinfunction "1_1") (pintype "passive"))
    )
    (net (code "32") (name "Net-(LED1-PadA)") (class "Default")
      (node (ref "LED1") (pin "A") (pinfunction "A_A") (pintype "passive"))
      (node (ref "R10") (pin "2") (pinfunction "2_2") (pintype "passive"))
    )
    (net (code "33") (name "Net-(LED2-PadA)") (class "Default")
      (node (ref "LED2") (pin "A") (pinfunction "A_A") (pintype "passive"))
      (node (ref "R2") (pin "2") (pinfunction "2_2") (pintype "passive"))
    )
    (net (code "34") (name "Net-(LED3-PadK)") (class "Default")
      (node (ref "LED3") (pin "K") (pinfunction "K_K") (pintype "passive"))
      (node (ref "R3") (pin "1") (pinfunction "1_1") (pintype "passive"))
    )
    (net (code "35") (name "Net-(LED4-PadK)") (class "Default")
      (node (ref "LED4") (pin "K") (pinfunction "K_K") (pintype "passive"))
      (node (ref "R4") (pin "2") (pinfunction "2_2") (pintype "passive"))
    )
    (net (code "36") (name "Net-(LED5-PadA)") (class "Default")
      (node (ref "LED5") (pin "A") (pinfunction "A_A") (pintype "passive"))
      (node (ref "R6") (pin "2") (pinfunction "2_2") (pintype "passive"))
    )
    (net (code "37") (name "Net-(LED6-PadK)") (class "Default")
      (node (ref "LED6") (pin "K") (pinfunction "K_K") (pintype "passive"))
      (node (ref "R7") (pin "2") (pinfunction "2_2") (pintype "passive"))
    )
    (net (code "38") (name "Net-(LED7-PadK)") (class "Default")
      (node (ref "LED7") (pin "K") (pinfunction "K_K") (pintype "passive"))
      (node (ref "R8") (pin "2") (pinfunction "2_2") (pintype "passive"))
    )
    (net (code "39") (name "Net-(LED8-PadK)") (class "Default")
      (node (ref "LED8") (pin "K") (pinfunction "K_K") (pintype "passive"))
      (node (ref "R12") (pin "2") (pinfunction "2_2") (pintype "passive"))
    )
    (net (code "40") (name "Net-(LED9-PadK)") (class "Default")
      (node (ref "LED9") (pin "K") (pinfunction "K_K") (pintype "passive"))
      (node (ref "R15") (pin "2") (pinfunction "2_2") (pintype "passive"))
    )
    (net (code "41") (name "Net-(LED10-PadK)") (class "Default")
      (node (ref "LED10") (pin "K") (pinfunction "K_K") (pintype "passive"))
      (node (ref "R17") (pin "2") (pinfunction "2_2") (pintype "passive"))
    )
    (net (code "42") (name "Net-(LED11-PadK)") (class "Default")
      (node (ref "LED11") (pin "K") (pinfunction "K_K") (pintype "passive"))
      (node (ref "R20") (pin "2") (pinfunction "2_2") (pintype "passive"))
    )
    (net (code "43") (name "Net-(LED12-PadK)") (class "Default")
      (node (ref "LED12") (pin "K") (pinfunction "K_K") (pintype "passive"))
      (node (ref "R23") (pin "2") (pinfunction "2_2") (pintype "passive"))
    )
    (net (code "44") (name "Net-(LED13-PadK)") (class "Default")
      (node (ref "LED13") (pin "K") (pinfunction "K_K") (pintype "passive"))
      (node (ref "R26") (pin "2") (pinfunction "2_2") (pintype "passive"))
    )
    (net (code "45") (name "Net-(LED14-PadK)") (class "Default")
      (node (ref "LED14") (pin "K") (pinfunction "K_K") (pintype "passive"))
      (node (ref "R29") (pin "2") (pinfunction "2_2") (pintype "passive"))
    )
    (net (code "46") (name "Net-(LED15-PadK)") (class "Default")
      (node (ref "LED15") (pin "K") (pinfunction "K_K") (pintype "passive"))
      (node (ref "R32") (pin "2") (pinfunction "2_2") (pintype "passive"))
    )
    (net (code "47") (name "Net-(LED16-PadK)") (class "Default")
      (node (ref "LED16") (pin "K") (pinfunction "K_K") (pintype "passive"))
      (node (ref "R35") (pin "2") (pinfunction "2_2") (pintype "passive"))
    )
    (net (code "48") (name "Net-(LED17-PadK)") (class "Default")
      (node (ref "LED17") (pin "K") (pinfunction "K_K") (pintype "passive"))
      (node (ref "R38") (pin "2") (pinfunction "2_2") (pintype "passive"))
    )
    (net (code "49") (name "Net-(LED18-PadK)") (class "Default")
      (node (ref "LED18") (pin "K") (pinfunction "K_K") (pintype "passive"))
      (node (ref "R41") (pin "2") (pinfunction "2_2") (pintype "passive"))
    )
    (net (code "50") (name "Net-(LED19-PadK)") (class "Default")
      (node (ref "LED19") (pin "K") (pinfunction "K_K") (pintype "passive"))
      (node (ref "R44") (pin "2") (pinfunction "2_2") (pintype "passive"))
    )
    (net (code "51") (name "Net-(LED20-PadA)") (class "Default")
      (node (ref "LED20") (pin "A") (pinfunction "A_A") (pintype "passive"))
      (node (ref "R48") (pin "2") (pinfunction "2_2") (pintype "passive"))
    )
    (net (code "52") (name "Net-(LED21-PadA)") (class "Default")
      (node (ref "LED21") (pin "A") (pinfunction "A_A") (pintype "passive"))
      (node (ref "R50") (pin "2") (pinfunction "2_2") (pintype "passive"))
    )
    (net (code "53") (name "Net-(LED22-PadA)") (class "Default")
      (node (ref "LED22") (pin "A") (pinfunction "A_A") (pintype "passive"))
      (node (ref "R52") (pin "2") (pinfunction "2_2") (pintype "passive"))
    )
    (net (code "54") (name "Net-(LED23-PadA)") (class "Default")
      (node (ref "LED23") (pin "A") (pinfunction "A_A") (pintype "passive"))
      (node (ref "R54") (pin "2") (pinfunction "2_2") (pintype "passive"))
    )
    (net (code "55") (name "Net-(LED24-PadA)") (class "Default")
      (node (ref "LED24") (pin "A") (pinfunction "A_A") (pintype "passive"))
      (node (ref "R62") (pin "2") (pinfunction "2_2") (pintype "passive"))
    )
    (net (code "56") (name "Net-(LED26-PadA)") (class "Default")
      (node (ref "LED26") (pin "A") (pinfunction "A_A") (pintype "passive"))
      (node (ref "R58") (pin "2") (pinfunction "2_2") (pintype "passive"))
    )
    (net (code "57") (name "Net-(LED27-PadA)") (class "Default")
      (node (ref "LED27") (pin "A") (pinfunction "A_A") (pintype "passive"))
      (node (ref "R56") (pin "2") (pinfunction "2_2") (pintype "passive"))
    )
    (net (code "58") (name "Net-(Q2-B)") (class "Default")
      (node (ref "Q2") (pin "1") (pinfunction "B_1") (pintype "bidirectional"))
      (node (ref "R22") (pin "2") (pinfunction "2_2") (pintype "passive"))
    )
    (net (code "59") (name "Net-(Q3-B)") (class "Default")
      (node (ref "Q3") (pin "1") (pinfunction "B_1") (pintype "bidirectional"))
      (node (ref "R25") (pin "2") (pinfunction "2_2") (pintype "passive"))
    )
    (net (code "60") (name "Net-(Q4-B)") (class "Default")
      (node (ref "Q4") (pin "1") (pinfunction "B_1") (pintype "bidirectional"))
      (node (ref "R28") (pin "2") (pinfunction "2_2") (pintype "passive"))
    )
    (net (code "61") (name "Net-(Q5-B)") (class "Default")
      (node (ref "Q5") (pin "1") (pinfunction "B_1") (pintype "bidirectional"))
      (node (ref "R31") (pin "2") (pinfunction "2_2") (pintype "passive"))
    )
    (net (code "62") (name "Net-(Q6-B)") (class "Default")
      (node (ref "Q6") (pin "1") (pinfunction "B_1") (pintype "bidirectional"))
      (node (ref "R34") (pin "2") (pinfunction "2_2") (pintype "passive"))
    )
    (net (code "63") (name "Net-(Q7-B)") (class "Default")
      (node (ref "Q7") (pin "1") (pinfunction "B_1") (pintype "bidirectional"))
      (node (ref "R37") (pin "2") (pinfunction "2_2") (pintype "passive"))
    )
    (net (code "64") (name "Net-(Q8-B)") (class "Default")
      (node (ref "Q8") (pin "1") (pinfunction "B_1") (pintype "bidirectional"))
      (node (ref "R40") (pin "2") (pinfunction "2_2") (pintype "passive"))
    )
    (net (code "65") (name "Net-(Q9-B)") (class "Default")
      (node (ref "Q9") (pin "1") (pinfunction "B_1") (pintype "bidirectional"))
      (node (ref "R43") (pin "2") (pinfunction "2_2") (pintype "passive"))
    )
    (net (code "66") (name "Net-(Q10-B)") (class "Default")
      (node (ref "Q10") (pin "1") (pinfunction "B_1") (pintype "bidirectional"))
      (node (ref "R46") (pin "2") (pinfunction "2_2") (pintype "passive"))
    )
    (net (code "67") (name "Net-(Q12-B)") (class "Default")
      (node (ref "Q12") (pin "1") (pinfunction "B_1") (pintype "bidirectional"))
      (node (ref "R19") (pin "2") (pinfunction "2_2") (pintype "passive"))
    )
    (net (code "68") (name "Net-(TR1-D)") (class "Default")
      (node (ref "R8") (pin "1") (pinfunction "1_1") (pintype "passive"))
      (node (ref "TR1") (pin "3") (pinfunction "D_3") (pintype "bidirectional"))
    )
    (net (code "69") (name "Net-(TR1-G)") (class "Default")
      (node (ref "R11") (pin "2") (pinfunction "2_2") (pintype "passive"))
      (node (ref "TR1") (pin "1") (pinfunction "G_1") (pintype "bidirectional"))
    )
    (net (code "70") (name "Net-(TR2-D)") (class "Default")
      (node (ref "R7") (pin "1") (pinfunction "1_1") (pintype "passive"))
      (node (ref "TR2") (pin "3") (pinfunction "D_3") (pintype "bidirectional"))
    )
    (net (code "71") (name "Net-(TR2-G)") (class "Default")
      (node (ref "R14") (pin "2") (pinfunction "2_2") (pintype "passive"))
      (node (ref "TR2") (pin "1") (pinfunction "G_1") (pintype "bidirectional"))
    )
    (net (code "72") (name "Net-(TR3-D)") (class "Default")
      (node (ref "R12") (pin "1") (pinfunction "1_1") (pintype "passive"))
      (node (ref "TR3") (pin "3") (pinfunction "D_3") (pintype "bidirectional"))
    )
    (net (code "73") (name "Net-(TR3-G)") (class "Default")
      (node (ref "R13") (pin "2") (pinfunction "2_2") (pintype "passive"))
      (node (ref "TR3") (pin "1") (pinfunction "G_1") (pintype "bidirectional"))
    )
    (net (code "74") (name "Net-(TR4-D)") (class "Default")
      (node (ref "R15") (pin "1") (pinfunction "1_1") (pintype "passive"))
      (node (ref "TR4") (pin "3") (pinfunction "D_3") (pintype "bidirectional"))
    )
    (net (code "75") (name "Net-(TR4-G)") (class "Default")
      (node (ref "R16") (pin "2") (pinfunction "2_2") (pintype "passive"))
      (node (ref "TR4") (pin "1") (pinfunction "G_1") (pintype "bidirectional"))
    )
    (net (code "76") (name "Net-(TR5-D)") (class "Default")
      (node (ref "R17") (pin "1") (pinfunction "1_1") (pintype "passive"))
      (node (ref "TR5") (pin "3") (pinfunction "D_3") (pintype "bidirectional"))
    )
    (net (code "77") (name "Net-(TR5-G)") (class "Default")
      (node (ref "R18") (pin "2") (pinfunction "2_2") (pintype "passive"))
      (node (ref "TR5") (pin "1") (pinfunction "G_1") (pintype "bidirectional"))
    )
    (net (code "78") (name "Net-(TR6-D)") (class "Default")
      (node (ref "R20") (pin "1") (pinfunction "1_1") (pintype "passive"))
      (node (ref "TR6") (pin "3") (pinfunction "D_3") (pintype "bidirectional"))
    )
    (net (code "79") (name "Net-(TR6-G)") (class "Default")
      (node (ref "R21") (pin "2") (pinfunction "2_2") (pintype "passive"))
      (node (ref "TR6") (pin "1") (pinfunction "G_1") (pintype "bidirectional"))
    )
    (net (code "80") (name "Net-(TR7-D)") (class "Default")
      (node (ref "R23") (pin "1") (pinfunction "1_1") (pintype "passive"))
      (node (ref "TR7") (pin "3") (pinfunction "D_3") (pintype "bidirectional"))
    )
    (net (code "81") (name "Net-(TR7-G)") (class "Default")
      (node (ref "R24") (pin "2") (pinfunction "2_2") (pintype "passive"))
      (node (ref "TR7") (pin "1") (pinfunction "G_1") (pintype "bidirectional"))
    )
    (net (code "82") (name "Net-(TR8-D)") (class "Default")
      (node (ref "R26") (pin "1") (pinfunction "1_1") (pintype "passive"))
      (node (ref "TR8") (pin "3") (pinfunction "D_3") (pintype "bidirectional"))
    )
    (net (code "83") (name "Net-(TR8-G)") (class "Default")
      (node (ref "R27") (pin "2") (pinfunction "2_2") (pintype "passive"))
      (node (ref "TR8") (pin "1") (pinfunction "G_1") (pintype "bidirectional"))
    )
    (net (code "84") (name "Net-(TR9-D)") (class "Default")
      (node (ref "R29") (pin "1") (pinfunction "1_1") (pintype "passive"))
      (node (ref "TR9") (pin "3") (pinfunction "D_3") (pintype "bidirectional"))
    )
    (net (code "85") (name "Net-(TR9-G)") (class "Default")
      (node (ref "R30") (pin "2") (pinfunction "2_2") (pintype "passive"))
      (node (ref "TR9") (pin "1") (pinfunction "G_1") (pintype "bidirectional"))
    )
    (net (code "86") (name "Net-(TR10-D)") (class "Default")
      (node (ref "R32") (pin "1") (pinfunction "1_1") (pintype "passive"))
      (node (ref "TR10") (pin "3") (pinfunction "D_3") (pintype "bidirectional"))
    )
    (net (code "87") (name "Net-(TR10-G)") (class "Default")
      (node (ref "R33") (pin "2") (pinfunction "2_2") (pintype "passive"))
      (node (ref "TR10") (pin "1") (pinfunction "G_1") (pintype "bidirectional"))
    )
    (net (code "88") (name "Net-(TR11-D)") (class "Default")
      (node (ref "R35") (pin "1") (pinfunction "1_1") (pintype "passive"))
      (node (ref "TR11") (pin "3") (pinfunction "D_3") (pintype "bidirectional"))
    )
    (net (code "89") (name "Net-(TR11-G)") (class "Default")
      (node (ref "R36") (pin "2") (pinfunction "2_2") (pintype "passive"))
      (node (ref "TR11") (pin "1") (pinfunction "G_1") (pintype "bidirectional"))
    )
    (net (code "90") (name "Net-(TR12-D)") (class "Default")
      (node (ref "R38") (pin "1") (pinfunction "1_1") (pintype "passive"))
      (node (ref "TR12") (pin "3") (pinfunction "D_3") (pintype "bidirectional"))
    )
    (net (code "91") (name "Net-(TR12-G)") (class "Default")
      (node (ref "R39") (pin "2") (pinfunction "2_2") (pintype "passive"))
      (node (ref "TR12") (pin "1") (pinfunction "G_1") (pintype "bidirectional"))
    )
    (net (code "92") (name "Net-(TR13-D)") (class "Default")
      (node (ref "R41") (pin "1") (pinfunction "1_1") (pintype "passive"))
      (node (ref "TR13") (pin "3") (pinfunction "D_3") (pintype "bidirectional"))
    )
    (net (code "93") (name "Net-(TR13-G)") (class "Default")
      (node (ref "R42") (pin "2") (pinfunction "2_2") (pintype "passive"))
      (node (ref "TR13") (pin "1") (pinfunction "G_1") (pintype "bidirectional"))
    )
    (net (code "94") (name "Net-(TR14-D)") (class "Default")
      (node (ref "R44") (pin "1") (pinfunction "1_1") (pintype "passive"))
      (node (ref "TR14") (pin "3") (pinfunction "D_3") (pintype "bidirectional"))
    )
    (net (code "95") (name "Net-(TR14-G)") (class "Default")
      (node (ref "R45") (pin "2") (pinfunction "2_2") (pintype "passive"))
      (node (ref "TR14") (pin "1") (pinfunction "G_1") (pintype "bidirectional"))
    )
    (net (code "96") (name "Net-(TR15-D)") (class "Default")
      (node (ref "LED20") (pin "K") (pinfunction "K_K") (pintype "passive"))
      (node (ref "TR15") (pin "3") (pinfunction "D_3") (pintype "bidirectional"))
    )
    (net (code "97") (name "Net-(TR15-G)") (class "Default")
      (node (ref "R47") (pin "2") (pinfunction "2_2") (pintype "passive"))
      (node (ref "TR15") (pin "1") (pinfunction "G_1") (pintype "bidirectional"))
    )
    (net (code "98") (name "Net-(TR16-D)") (class "Default")
      (node (ref "LED21") (pin "K") (pinfunction "K_K") (pintype "passive"))
      (node (ref "TR16") (pin "3") (pinfunction "D_3") (pintype "bidirectional"))
    )
    (net (code "99") (name "Net-(TR16-G)") (class "Default")
      (node (ref "R49") (pin "2") (pinfunction "2_2") (pintype "passive"))
      (node (ref "TR16") (pin "1") (pinfunction "G_1") (pintype "bidirectional"))
    )
    (net (code "100") (name "Net-(TR17-D)") (class "Default")
      (node (ref "LED27") (pin "K") (pinfunction "K_K") (pintype "passive"))
      (node (ref "TR17") (pin "3") (pinfunction "D_3") (pintype "bidirectional"))
    )
    (net (code "101") (name "Net-(TR17-G)") (class "Default")
      (node (ref "R55") (pin "2") (pinfunction "2_2") (pintype "passive"))
      (node (ref "TR17") (pin "1") (pinfunction "G_1") (pintype "bidirectional"))
    )
    (net (code "102") (name "Net-(TR18-D)") (class "Default")
      (node (ref "LED26") (pin "K") (pinfunction "K_K") (pintype "passive"))
      (node (ref "TR18") (pin "3") (pinfunction "D_3") (pintype "bidirectional"))
    )
    (net (code "103") (name "Net-(TR18-G)") (class "Default")
      (node (ref "R57") (pin "2") (pinfunction "2_2") (pintype "passive"))
      (node (ref "TR18") (pin "1") (pinfunction "G_1") (pintype "bidirectional"))
    )
    (net (code "104") (name "Net-(TR19-D)") (class "Default")
      (node (ref "LED5") (pin "K") (pinfunction "K_K") (pintype "passive"))
      (node (ref "TR19") (pin "3") (pinfunction "D_3") (pintype "bidirectional"))
    )
    (net (code "105") (name "Net-(TR19-G)") (class "Default")
      (node (ref "R5") (pin "2") (pinfunction "2_2") (pintype "passive"))
      (node (ref "TR19") (pin "1") (pinfunction "G_1") (pintype "bidirectional"))
    )
    (net (code "106") (name "Net-(TR20-D)") (class "Default")
      (node (ref "LED24") (pin "K") (pinfunction "K_K") (pintype "passive"))
      (node (ref "TR20") (pin "3") (pinfunction "D_3") (pintype "bidirectional"))
    )
    (net (code "107") (name "Net-(TR20-G)") (class "Default")
      (node (ref "R61") (pin "2") (pinfunction "2_2") (pintype "passive"))
      (node (ref "TR20") (pin "1") (pinfunction "G_1") (pintype "bidirectional"))
    )
    (net (code "108") (name "Net-(TR21-D)") (class "Default")
      (node (ref "LED23") (pin "K") (pinfunction "K_K") (pintype "passive"))
      (node (ref "TR21") (pin "3") (pinfunction "D_3") (pintype "bidirectional"))
    )
    (net (code "109") (name "Net-(TR21-G)") (class "Default")
      (node (ref "R53") (pin "2") (pinfunction "2_2") (pintype "passive"))
      (node (ref "TR21") (pin "1") (pinfunction "G_1") (pintype "bidirectional"))
    )
    (net (code "110") (name "Net-(TR22-D)") (class "Default")
      (node (ref "LED22") (pin "K") (pinfunction "K_K") (pintype "passive"))
      (node (ref "TR22") (pin "3") (pinfunction "D_3") (pintype "bidirectional"))
    )
    (net (code "111") (name "Net-(TR22-G)") (class "Default")
      (node (ref "R51") (pin "2") (pinfunction "2_2") (pintype "passive"))
      (node (ref "TR22") (pin "1") (pinfunction "G_1") (pintype "bidirectional"))
    )
    (net (code "112") (name "PA2") (class "Default")
      (node (ref "J1") (pin "23") (pinfunction "23_23") (pintype "bidirectional"))
      (node (ref "J1") (pin "24") (pinfunction "24_24") (pintype "bidirectional"))
      (node (ref "Q5") (pin "2") (pinfunction "E_2") (pintype "bidirectional"))
    )
    (net (code "113") (name "PA3") (class "Default")
      (node (ref "J1") (pin "25") (pinfunction "25_25") (pintype "bidirectional"))
      (node (ref "J1") (pin "26") (pinfunction "26_26") (pintype "bidirectional"))
      (node (ref "Q10") (pin "2") (pinfunction "E_2") (pintype "bidirectional"))
    )
    (net (code "114") (name "PA15") (class "Default")
      (node (ref "J3") (pin "25") (pinfunction "25_25") (pintype "bidirectional"))
      (node (ref "J3") (pin "26") (pinfunction "26_26") (pintype "bidirectional"))
      (node (ref "Q12") (pin "2") (pinfunction "E_2") (pintype "bidirectional"))
    )
    (net (code "115") (name "PB0") (class "Default")
      (node (ref "IC2") (pin "25") (pinfunction "PB0_25") (pintype "bidirectional"))
      (node (ref "J6") (pin "23") (pinfunction "23_23") (pintype "bidirectional"))
      (node (ref "J6") (pin "24") (pinfunction "24_24") (pintype "bidirectional"))
      (node (ref "JP2") (pin "3") (pinfunction "3_3") (pintype "passive"))
      (node (ref "Q4") (pin "2") (pinfunction "E_2") (pintype "bidirectional"))
    )
    (net (code "116") (name "PB1") (class "Default")
      (node (ref "IC2") (pin "26") (pinfunction "PB1_26") (pintype "bidirectional"))
      (node (ref "J6") (pin "25") (pinfunction "25_25") (pintype "bidirectional"))
      (node (ref "J6") (pin "26") (pinfunction "26_26") (pintype "bidirectional"))
      (node (ref "JP2") (pin "2") (pinfunction "2_2") (pintype "passive"))
      (node (ref "Q9") (pin "2") (pinfunction "E_2") (pintype "bidirectional"))
    )
    (net (code "117") (name "PB2") (class "Default")
      (node (ref "IC2") (pin "27") (pinfunction "PB2_27") (pintype "bidirectional"))
      (node (ref "JP2") (pin "1") (pinfunction "1_1") (pintype "passive"))
    )
    (net (code "118") (name "PB3") (class "Default")
      (node (ref "J3") (pin "23") (pinfunction "23_23") (pintype "bidirectional"))
      (node (ref "J3") (pin "24") (pinfunction "24_24") (pintype "bidirectional"))
      (node (ref "Q6") (pin "2") (pinfunction "E_2") (pintype "bidirectional"))
    )
    (net (code "119") (name "PB10") (class "Default")
      (node (ref "J5") (pin "23") (pinfunction "23_23") (pintype "bidirectional"))
      (node (ref "J5") (pin "24") (pinfunction "24_24") (pintype "bidirectional"))
      (node (ref "Q3") (pin "2") (pinfunction "E_2") (pintype "bidirectional"))
    )
    (net (code "120") (name "PB11") (class "Default")
      (node (ref "J5") (pin "25") (pinfunction "25_25") (pintype "bidirectional"))
      (node (ref "J5") (pin "26") (pinfunction "26_26") (pintype "bidirectional"))
      (node (ref "Q8") (pin "2") (pinfunction "E_2") (pintype "bidirectional"))
    )
    (net (code "121") (name "PB14") (class "Default")
      (node (ref "J4") (pin "25") (pinfunction "25_25") (pintype "bidirectional"))
      (node (ref "J4") (pin "26") (pinfunction "26_26") (pintype "bidirectional"))
      (node (ref "Q7") (pin "2") (pinfunction "E_2") (pintype "bidirectional"))
    )
    (net (code "122") (name "PB15") (class "Default")
      (node (ref "J4") (pin "23") (pinfunction "23_23") (pintype "bidirectional"))
      (node (ref "J4") (pin "24") (pinfunction "24_24") (pintype "bidirectional"))
      (node (ref "Q2") (pin "2") (pinfunction "E_2") (pintype "bidirectional"))
    )
    (net (code "123") (name "PC0") (class "Default")
      (node (ref "C28") (pin "2") (pinfunction "2_2") (pintype "bidirectional"))
      (node (ref "IC2") (pin "8") (pinfunction "PC0_8") (pintype "bidirectional"))
      (node (ref "JP1") (pin "1") (pinfunction "1_1") (pintype "passive"))
      (node (ref "LED4") (pin "A") (pinfunction "A_A") (pintype "passive"))
      (node (ref "S1") (pin "A1") (pinfunction "NO_1_A1") (pintype "bidirectional"))
    )
    (net (code "124") (name "PC1") (class "Default")
      (node (ref "IC2") (pin "9") (pinfunction "PC1_9") (pintype "bidirectional"))
      (node (ref "JP1") (pin "2") (pinfunction "2_2") (pintype "passive"))
    )
    (net (code "125") (name "PC2") (class "Default")
      (node (ref "IC2") (pin "10") (pinfunction "PC2_10") (pintype "bidirectional"))
      (node (ref "JP1") (pin "4") (pinfunction "4_4") (pintype "passive"))
    )
    (net (code "126") (name "PC3") (class "Default")
      (node (ref "IC2") (pin "11") (pinfunction "PC3_11") (pintype "bidirectional"))
      (node (ref "JP1") (pin "6") (pinfunction "6_6") (pintype "passive"))
    )
    (net (code "127") (name "PC4") (class "Default")
      (node (ref "IC2") (pin "24") (pinfunction "PC4_24") (pintype "bidirectional"))
      (node (ref "JP2") (pin "4") (pinfunction "4_4") (pintype "passive"))
    )
    (net (code "128") (name "PC10") (class "Default")
      (node (ref "IC2") (pin "51") (pinfunction "PC10_51") (pintype "bidirectional"))
      (node (ref "R16") (pin "1") (pinfunction "1_1") (pintype "passive"))
    )
    (net (code "129") (name "PC11") (class "Default")
      (node (ref "IC2") (pin "52") (pinfunction "PC11_52") (pintype "bidirectional"))
      (node (ref "R13") (pin "1") (pinfunction "1_1") (pintype "passive"))
    )
    (net (code "130") (name "PC12") (class "Default")
      (node (ref "IC2") (pin "53") (pinfunction "PC12_53") (pintype "bidirectional"))
      (node (ref "R11") (pin "1") (pinfunction "1_1") (pintype "passive"))
    )
    (net (code "131") (name "PC13") (class "Default")
      (node (ref "IC2") (pin "2") (pinfunction "PC13_2") (pintype "bidirectional"))
      (node (ref "JP1") (pin "5") (pinfunction "5_5") (pintype "passive"))
    )
    (net (code "132") (name "PC14") (class "Default")
      (node (ref "IC2") (pin "3") (pinfunction "PC14-OSC32_IN_3") (pintype "bidirectional"))
      (node (ref "JP1") (pin "3") (pinfunction "3_3") (pintype "passive"))
    )
    (net (code "133") (name "PD2") (class "Default")
      (node (ref "IC2") (pin "54") (pinfunction "PD2_54") (pintype "bidirectional"))
      (node (ref "R14") (pin "1") (pinfunction "1_1") (pintype "passive"))
    )
    (net (code "134") (name "SPI_MISO") (class "Default")
      (node (ref "IC2") (pin "22") (pinfunction "PA6_22") (pintype "bidirectional"))
      (node (ref "X7") (pin "2") (pinfunction "2_2") (pintype "passive"))
    )
    (net (code "135") (name "SPI_MOSI") (class "Default")
      (node (ref "IC2") (pin "23") (pinfunction "PA7_23") (pintype "bidirectional"))
      (node (ref "X7") (pin "1") (pinfunction "1_1") (pintype "passive"))
    )
    (net (code "136") (name "SPI_NSS") (class "Default")
      (node (ref "IC2") (pin "20") (pinfunction "PA4_20") (pintype "bidirectional"))
      (node (ref "X7") (pin "4") (pinfunction "4_4") (pintype "passive"))
    )
    (net (code "137") (name "SPI_SCK") (class "Default")
      (node (ref "IC2") (pin "21") (pinfunction "PA5_21") (pintype "bidirectional"))
      (node (ref "X7") (pin "3") (pinfunction "3_3") (pintype "passive"))
    )
    (net (code "138") (name "SWCLK") (class "Default")
      (node (ref "IC2") (pin "49") (pinfunction "PA14_49") (pintype "bidirectional"))
      (node (ref "SL1") (pin "2") (pinfunction "2_2") (pintype "passive"))
    )
    (net (code "139") (name "SWDIO") (class "Default")
      (node (ref "IC2") (pin "46") (pinfunction "PA13_46") (pintype "bidirectional"))
      (node (ref "SL1") (pin "4") (pinfunction "4_4") (pintype "passive"))
    )
    (net (code "140") (name "USART_RX") (class "Default")
      (node (ref "IC2") (pin "29") (pinfunction "PB11_29") (pintype "bidirectional"))
      (node (ref "X8") (pin "2") (pinfunction "2_2") (pintype "passive"))
    )
    (net (code "141") (name "USRAT_TX") (class "Default")
      (node (ref "IC2") (pin "28") (pinfunction "PB10_28") (pintype "bidirectional"))
      (node (ref "X8") (pin "1") (pinfunction "1_1") (pintype "passive"))
    )
    (net (code "142") (name "VCAP_1") (class "Default")
      (node (ref "C20") (pin "2") (pinfunction "2_2") (pintype "bidirectional"))
      (node (ref "C21") (pin "2") (pinfunction "2_2") (pintype "bidirectional"))
    )
    (net (code "143") (name "unconnected-(IC2-PA10-Pad43)") (class "Default")
      (node (ref "IC2") (pin "43") (pinfunction "PA10_43") (pintype "bidirectional"))
    )
    (net (code "144") (name "unconnected-(IC2-PB12-Pad33)") (class "Default")
      (node (ref "IC2") (pin "33") (pinfunction "PB12_33") (pintype "bidirectional"))
    )
    (net (code "145") (name "unconnected-(IC2-PB13-Pad34)") (class "Default")
      (node (ref "IC2") (pin "34") (pinfunction "PB13_34") (pintype "bidirectional"))
    )
    (net (code "146") (name "unconnected-(IC2-PC15-OSC32_OUT-Pad4)") (class "Default")
      (node (ref "IC2") (pin "4") (pinfunction "PC15-OSC32_OUT_4") (pintype "bidirectional"))
    )
    (net (code "147") (name "unconnected-(IC2-PH0-OSC_IN-Pad5)") (class "Default")
      (node (ref "IC2") (pin "5") (pinfunction "PH0-OSC_IN_5") (pintype "bidirectional"))
    )
    (net (code "148") (name "unconnected-(IC2-PH1-OSC_OUT-Pad6)") (class "Default")
      (node (ref "IC2") (pin "6") (pinfunction "PH1-OSC_OUT_6") (pintype "bidirectional"))
    )
    (net (code "149") (name "unconnected-(J2-PadMH1)") (class "Default")
      (node (ref "J2") (pin "MH1") (pinfunction "MH1_MH1") (pintype "bidirectional"))
    )
    (net (code "150") (name "unconnected-(J2-PadMH2)") (class "Default")
      (node (ref "J2") (pin "MH2") (pinfunction "MH2_MH2") (pintype "bidirectional"))
    )
    (net (code "151") (name "unconnected-(J2-PadMH3)") (class "Default")
      (node (ref "J2") (pin "MH3") (pinfunction "MH3_MH3") (pintype "bidirectional"))
    )
    (net (code "152") (name "unconnected-(J2-PadMH4)") (class "Default")
      (node (ref "J2") (pin "MH4") (pinfunction "MH4_MH4") (pintype "bidirectional"))
    )
    (net (code "153") (name "unconnected-(S1-COM_2-PadD1)") (class "Default")
      (node (ref "S1") (pin "D1") (pinfunction "COM_2_D1") (pintype "bidirectional"))
    )
    (net (code "154") (name "unconnected-(S1-NO_2-PadB1)") (class "Default")
      (node (ref "S1") (pin "B1") (pinfunction "NO_2_B1") (pintype "bidirectional"))
    )
    (net (code "155") (name "unconnected-(S2-NO_2-PadB1)") (class "Default")
      (node (ref "S2") (pin "B1") (pinfunction "NO_2_B1") (pintype "bidirectional"))
    )
    (net (code "156") (name "unconnected-(SL1-Pad6)") (class "Default")
      (node (ref "SL1") (pin "6") (pinfunction "6_6") (pintype "passive"))
    )
    (net (code "157") (name "unconnected-(X1-Pad2)") (class "Default")
      (node (ref "X1") (pin "2") (pinfunction "2_2") (pintype "passive"))
    )
    (net (code "158") (name "unconnected-(X2-Pad2)") (class "Default")
      (node (ref "X2") (pin "2") (pinfunction "2_2") (pintype "passive"))
    )
    (net (code "159") (name "unconnected-(X5-Pad2)") (class "Default")
      (node (ref "X5") (pin "2") (pinfunction "2_2") (pintype "passive"))
    )
    (net (code "160") (name "unconnected-(X6-Pad2)") (class "Default")
      (node (ref "X6") (pin "2") (pinfunction "2_2") (pintype "passive"))
    )
  )
)
